# fullCURRENT_power_motor_drive.net
KiCad netlist of a schematic drawn in Altium Designer
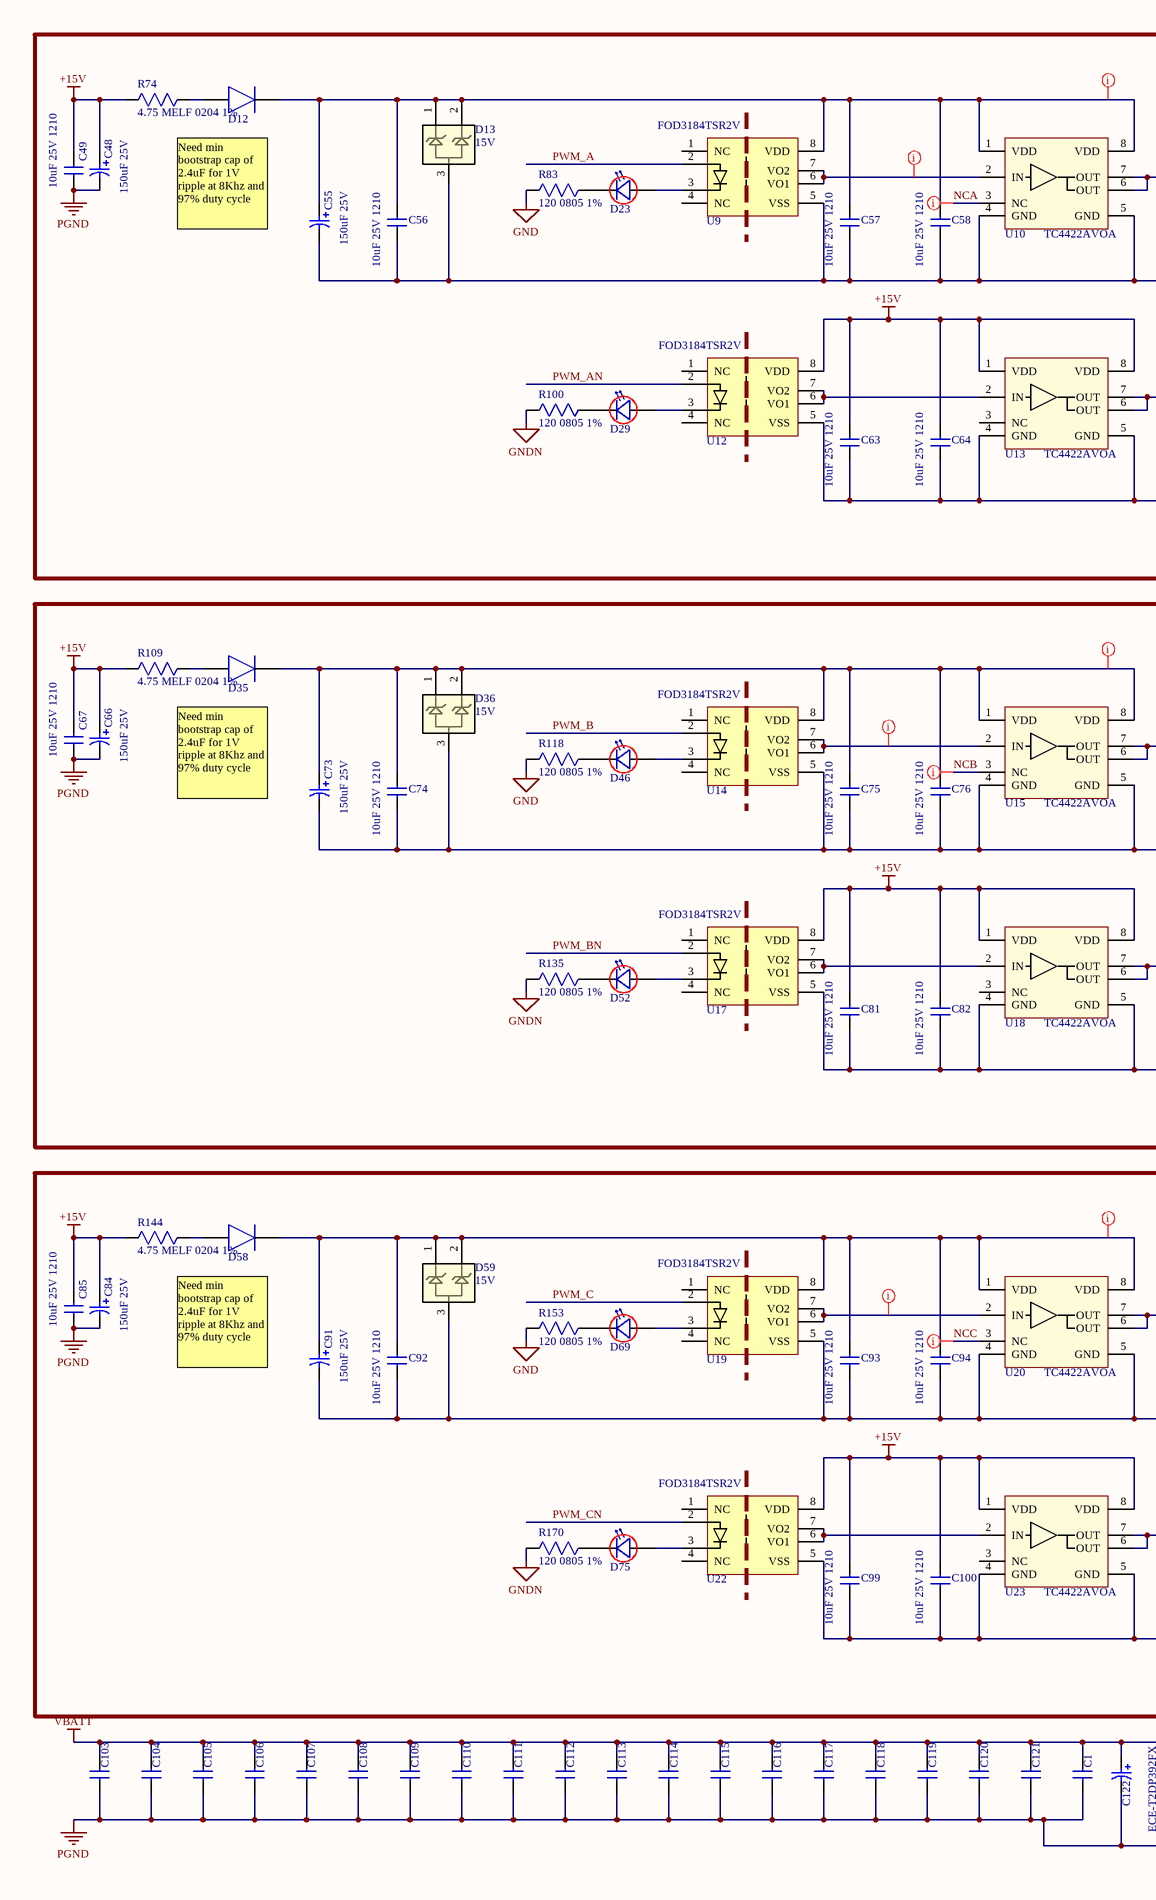
[diagram p0: fullCURRENT power motor drive.SchDoc, left]
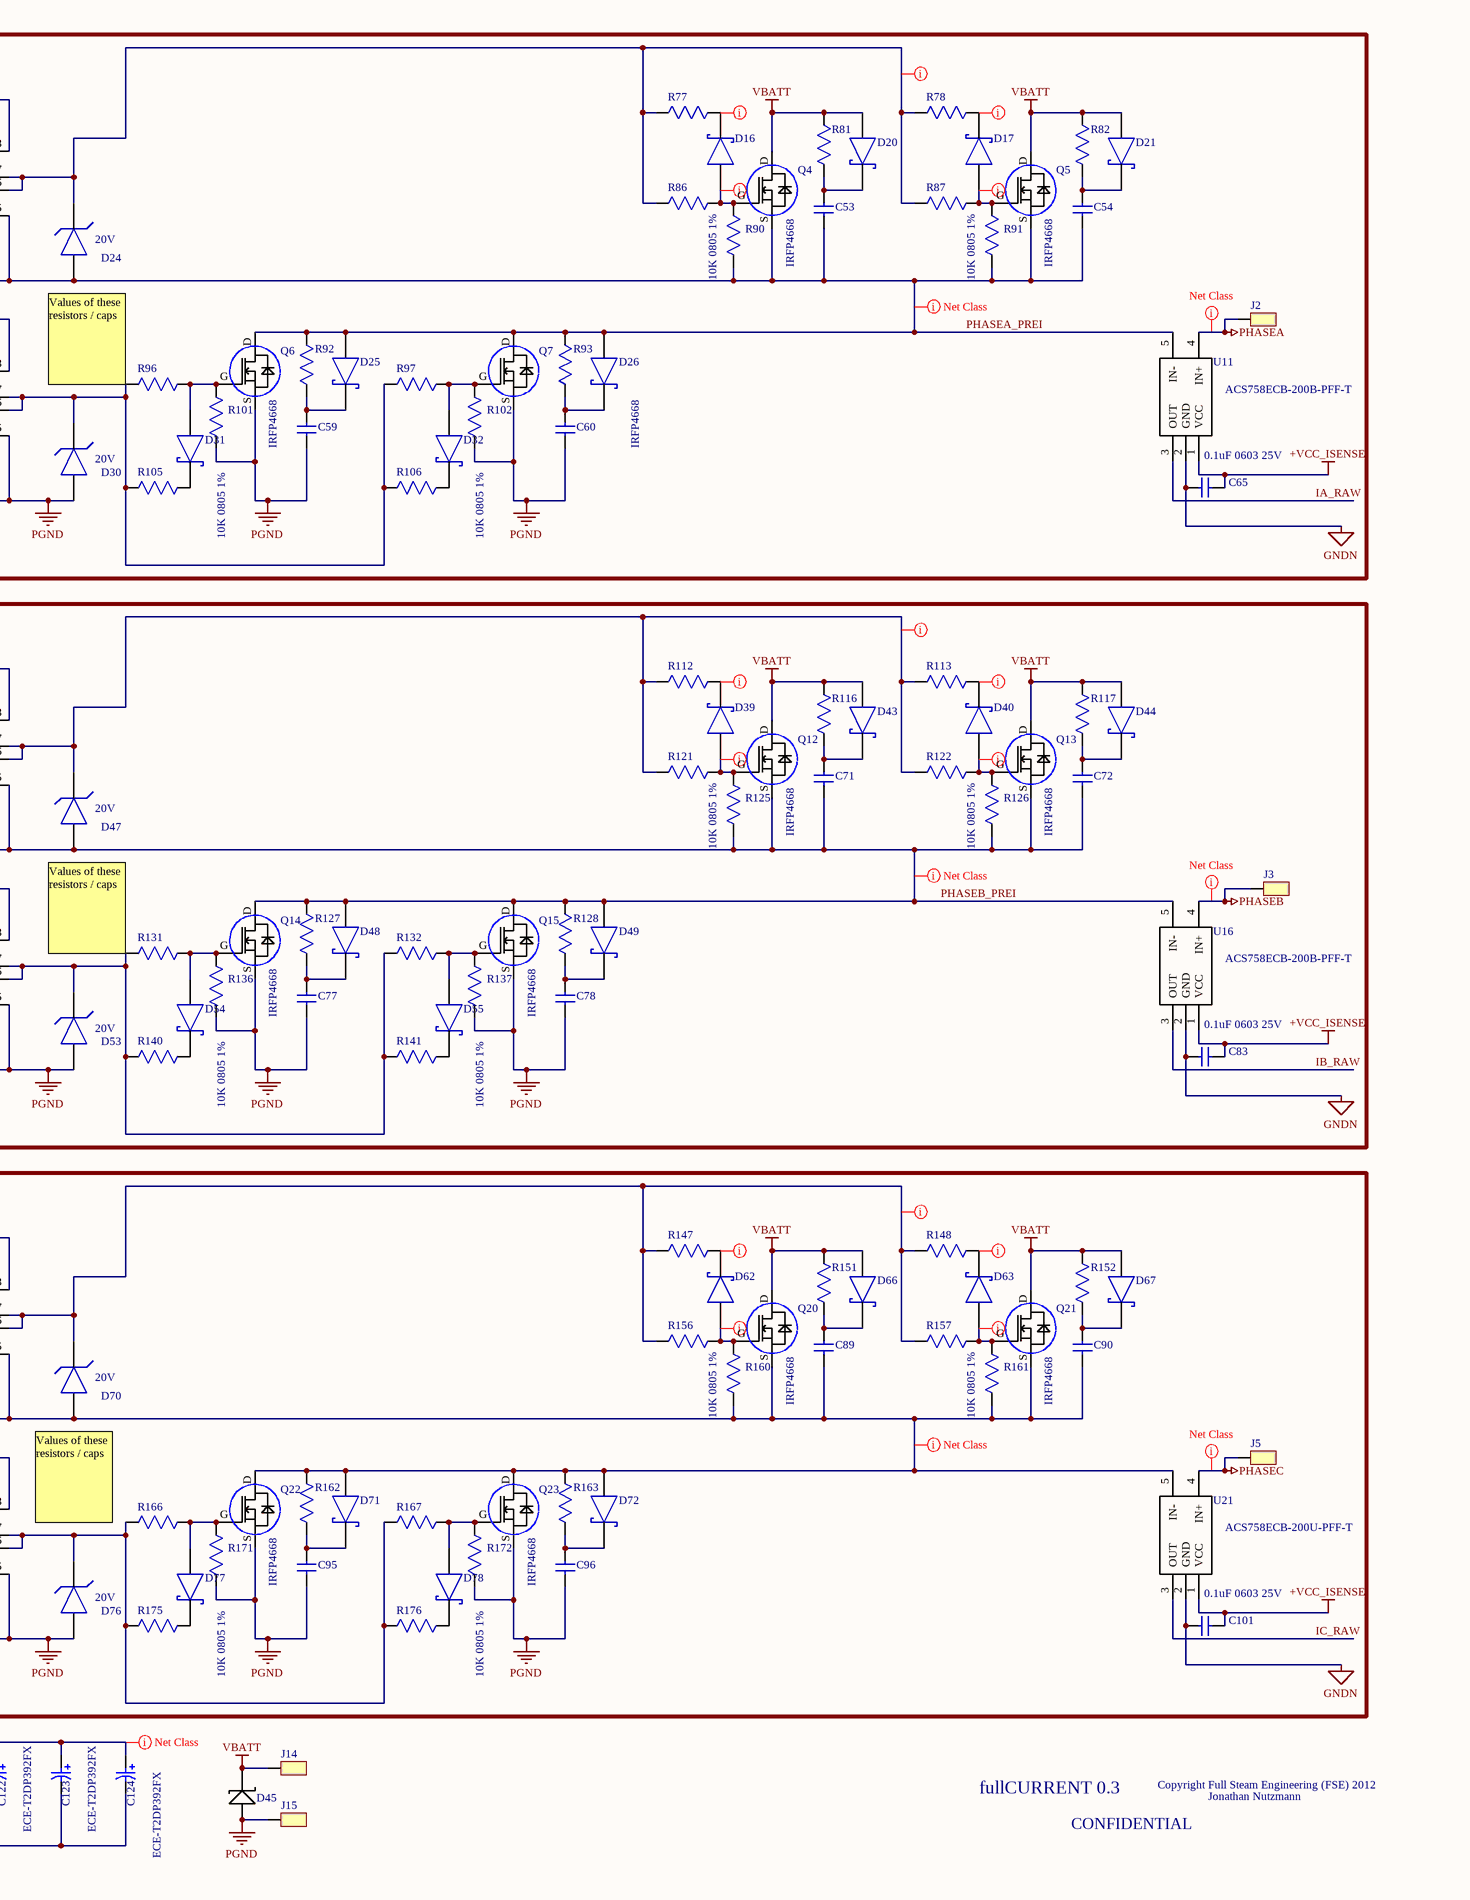
[diagram p1: fullCURRENT power motor drive.SchDoc, right]

(export (version "E")
  (design (tool "Eeschema 10.0.6"))
  (components
    (comp (ref "C1")
      (value "CAP 1210")
      (footprint "1825_CAPACITOR")
      (description "CAP CER 1UF 250V 10% X7R 1825")
      (libsource (lib "altium-import") (part "root_1_C_1210_"))
    )
    (comp (ref "C48")
      (value "150uF 25V")
      (footprint "CAPPR2.5-6.3x11")
      (description "CAP ALUM 150UF 25V 20% RADIAL")
      (fields (field (name "Comment") "C_UMA1E330MDD"))
      (libsource (lib "Nutz") (part "C_UMA1E330MDD"))
    )
    (comp (ref "C49")
      (value "10uF 25V 1210")
      (footprint "1210_Capacitor")
      (description "CAP CER 10UF 25V 10% X7R 1210")
      (fields (field (name "Comment") "CAP 1210"))
      (libsource (lib "c3_SchLib") (part "C_1210"))
    )
    (comp (ref "C53")
      (value "CAP 1210")
      (footprint "1210_Capacitor")
      (description "CAP CERM 1210")
      (libsource (lib "Nutz") (part "C_1210"))
    )
    (comp (ref "C54")
      (value "CAP 1210")
      (footprint "1210_Capacitor")
      (description "CAP CERM 1210")
      (libsource (lib "Nutz") (part "C_1210"))
    )
    (comp (ref "C55")
      (value "150uF 25V")
      (footprint "CAPPR2.5-6.3x11")
      (description "CAP ALUM 150UF 25V 20% RADIAL")
      (fields (field (name "Comment") "C_UMA1E330MDD"))
      (libsource (lib "Nutz") (part "C_UMA1E330MDD"))
    )
    (comp (ref "C56")
      (value "10uF 25V 1210")
      (footprint "1210_Capacitor")
      (description "CAP CER 10UF 25V 10% X7R 1210")
      (fields (field (name "Comment") "CAP 1210"))
      (libsource (lib "c3_SchLib") (part "C_1210"))
    )
    (comp (ref "C57")
      (value "10uF 25V 1210")
      (footprint "1210_Capacitor")
      (description "CAP CER 10UF 25V 10% X7R 1210")
      (fields (field (name "Comment") "CAP 1210"))
      (libsource (lib "c3_SchLib") (part "C_1210"))
    )
    (comp (ref "C58")
      (value "10uF 25V 1210")
      (footprint "1210_Capacitor")
      (description "CAP CER 10UF 25V 10% X7R 1210")
      (fields (field (name "Comment") "CAP 1210"))
      (libsource (lib "c3_SchLib") (part "C_1210"))
    )
    (comp (ref "C59")
      (value "CAP 1210")
      (footprint "1210_Capacitor")
      (description "CAP CERM 1210")
      (libsource (lib "Nutz") (part "C_1210"))
    )
    (comp (ref "C60")
      (value "CAP 1210")
      (footprint "1210_Capacitor")
      (description "CAP CERM 1210")
      (libsource (lib "Nutz") (part "C_1210"))
    )
    (comp (ref "C63")
      (value "10uF 25V 1210")
      (footprint "1210_Capacitor")
      (description "CAP CER 10UF 25V 10% X7R 1210")
      (fields (field (name "Comment") "CAP 1210"))
      (libsource (lib "c3_SchLib") (part "C_1210"))
    )
    (comp (ref "C64")
      (value "10uF 25V 1210")
      (footprint "1210_Capacitor")
      (description "CAP CER 10UF 25V 10% X7R 1210")
      (fields (field (name "Comment") "CAP 1210"))
      (libsource (lib "c3_SchLib") (part "C_1210"))
    )
    (comp (ref "C65")
      (value "0.1uF 0603 25V")
      (footprint "0805_CAPACITOR")
      (description "CAP CERM 0.1uF 0603 X7R")
      (fields (field (name "Comment") "CAP 0603"))
      (libsource (lib "Nutz") (part "C_0603"))
    )
    (comp (ref "C66")
      (value "150uF 25V")
      (footprint "CAPPR2.5-6.3x11")
      (description "CAP ALUM 150UF 25V 20% RADIAL")
      (fields (field (name "Comment") "C_UMA1E330MDD"))
      (libsource (lib "Nutz") (part "C_UMA1E330MDD"))
    )
    (comp (ref "C67")
      (value "10uF 25V 1210")
      (footprint "1210_Capacitor")
      (description "CAP CER 10UF 25V 10% X7R 1210")
      (fields (field (name "Comment") "CAP 1210"))
      (libsource (lib "c3_SchLib") (part "C_1210"))
    )
    (comp (ref "C71")
      (value "CAP 1210")
      (footprint "1210_Capacitor")
      (description "CAP CERM 1210")
      (libsource (lib "Nutz") (part "C_1210"))
    )
    (comp (ref "C72")
      (value "CAP 1210")
      (footprint "1210_Capacitor")
      (description "CAP CERM 1210")
      (libsource (lib "Nutz") (part "C_1210"))
    )
    (comp (ref "C73")
      (value "150uF 25V")
      (footprint "CAPPR2.5-6.3x11")
      (description "CAP ALUM 150UF 25V 20% RADIAL")
      (fields (field (name "Comment") "C_UMA1E330MDD"))
      (libsource (lib "Nutz") (part "C_UMA1E330MDD"))
    )
    (comp (ref "C74")
      (value "10uF 25V 1210")
      (footprint "1210_Capacitor")
      (description "CAP CER 10UF 25V 10% X7R 1210")
      (fields (field (name "Comment") "CAP 1210"))
      (libsource (lib "c3_SchLib") (part "C_1210"))
    )
    (comp (ref "C75")
      (value "10uF 25V 1210")
      (footprint "1210_Capacitor")
      (description "CAP CER 10UF 25V 10% X7R 1210")
      (fields (field (name "Comment") "CAP 1210"))
      (libsource (lib "c3_SchLib") (part "C_1210"))
    )
    (comp (ref "C76")
      (value "10uF 25V 1210")
      (footprint "1210_Capacitor")
      (description "CAP CER 10UF 25V 10% X7R 1210")
      (fields (field (name "Comment") "CAP 1210"))
      (libsource (lib "c3_SchLib") (part "C_1210"))
    )
    (comp (ref "C77")
      (value "CAP 1210")
      (footprint "1210_Capacitor")
      (description "CAP CERM 1210")
      (libsource (lib "Nutz") (part "C_1210"))
    )
    (comp (ref "C78")
      (value "CAP 1210")
      (footprint "1210_Capacitor")
      (description "CAP CERM 1210")
      (libsource (lib "Nutz") (part "C_1210"))
    )
    (comp (ref "C81")
      (value "10uF 25V 1210")
      (footprint "1210_Capacitor")
      (description "CAP CER 10UF 25V 10% X7R 1210")
      (fields (field (name "Comment") "CAP 1210"))
      (libsource (lib "c3_SchLib") (part "C_1210"))
    )
    (comp (ref "C82")
      (value "10uF 25V 1210")
      (footprint "1210_Capacitor")
      (description "CAP CER 10UF 25V 10% X7R 1210")
      (fields (field (name "Comment") "CAP 1210"))
      (libsource (lib "c3_SchLib") (part "C_1210"))
    )
    (comp (ref "C83")
      (value "0.1uF 0603 25V")
      (footprint "0805_CAPACITOR")
      (description "CAP CERM 0.1uF 0603 X7R")
      (fields (field (name "Comment") "CAP 0603"))
      (libsource (lib "Nutz") (part "C_0603"))
    )
    (comp (ref "C84")
      (value "150uF 25V")
      (footprint "CAPPR2.5-6.3x11")
      (description "CAP ALUM 150UF 25V 20% RADIAL")
      (fields (field (name "Comment") "C_UMA1E330MDD"))
      (libsource (lib "Nutz") (part "C_UMA1E330MDD"))
    )
    (comp (ref "C85")
      (value "10uF 25V 1210")
      (footprint "1210_Capacitor")
      (description "CAP CER 10UF 25V 10% X7R 1210")
      (fields (field (name "Comment") "CAP 1210"))
      (libsource (lib "c3_SchLib") (part "C_1210"))
    )
    (comp (ref "C89")
      (value "CAP 1210")
      (footprint "1210_Capacitor")
      (description "CAP CERM 1210")
      (libsource (lib "Nutz") (part "C_1210"))
    )
    (comp (ref "C90")
      (value "CAP 1210")
      (footprint "1210_Capacitor")
      (description "CAP CERM 1210")
      (libsource (lib "Nutz") (part "C_1210"))
    )
    (comp (ref "C91")
      (value "150uF 25V")
      (footprint "CAPPR2.5-6.3x11")
      (description "CAP ALUM 150UF 25V 20% RADIAL")
      (fields (field (name "Comment") "C_UMA1E330MDD"))
      (libsource (lib "Nutz") (part "C_UMA1E330MDD"))
    )
    (comp (ref "C92")
      (value "10uF 25V 1210")
      (footprint "1210_Capacitor")
      (description "CAP CER 10UF 25V 10% X7R 1210")
      (fields (field (name "Comment") "CAP 1210"))
      (libsource (lib "c3_SchLib") (part "C_1210"))
    )
    (comp (ref "C93")
      (value "10uF 25V 1210")
      (footprint "1210_Capacitor")
      (description "CAP CER 10UF 25V 10% X7R 1210")
      (fields (field (name "Comment") "CAP 1210"))
      (libsource (lib "c3_SchLib") (part "C_1210"))
    )
    (comp (ref "C94")
      (value "10uF 25V 1210")
      (footprint "1210_Capacitor")
      (description "CAP CER 10UF 25V 10% X7R 1210")
      (fields (field (name "Comment") "CAP 1210"))
      (libsource (lib "c3_SchLib") (part "C_1210"))
    )
    (comp (ref "C95")
      (value "CAP 1210")
      (footprint "1210_Capacitor")
      (description "CAP CERM 1210")
      (libsource (lib "Nutz") (part "C_1210"))
    )
    (comp (ref "C96")
      (value "CAP 1210")
      (footprint "1210_Capacitor")
      (description "CAP CERM 1210")
      (libsource (lib "Nutz") (part "C_1210"))
    )
    (comp (ref "C99")
      (value "10uF 25V 1210")
      (footprint "1210_Capacitor")
      (description "CAP CER 10UF 25V 10% X7R 1210")
      (fields (field (name "Comment") "CAP 1210"))
      (libsource (lib "c3_SchLib") (part "C_1210"))
    )
    (comp (ref "C100")
      (value "10uF 25V 1210")
      (footprint "1210_Capacitor")
      (description "CAP CER 10UF 25V 10% X7R 1210")
      (fields (field (name "Comment") "CAP 1210"))
      (libsource (lib "c3_SchLib") (part "C_1210"))
    )
    (comp (ref "C101")
      (value "0.1uF 0603 25V")
      (footprint "0805_CAPACITOR")
      (description "CAP CERM 0.1uF 0603 X7R")
      (fields (field (name "Comment") "CAP 0603"))
      (libsource (lib "Nutz") (part "C_0603"))
    )
    (comp (ref "C103")
      (value "CAP 1210")
      (footprint "1825_CAPACITOR")
      (description "CAP CER 1UF 250V 10% X7R 1825")
      (libsource (lib "altium-import") (part "root_1_C_1210_"))
    )
    (comp (ref "C104")
      (value "CAP 1210")
      (footprint "1825_CAPACITOR")
      (description "CAP CER 1UF 250V 10% X7R 1825")
      (libsource (lib "altium-import") (part "root_1_C_1210_"))
    )
    (comp (ref "C105")
      (value "CAP 1210")
      (footprint "1825_CAPACITOR")
      (description "CAP CER 1UF 250V 10% X7R 1825")
      (libsource (lib "altium-import") (part "root_1_C_1210_"))
    )
    (comp (ref "C106")
      (value "CAP 1210")
      (footprint "1825_CAPACITOR")
      (description "CAP CER 1UF 250V 10% X7R 1825")
      (libsource (lib "altium-import") (part "root_1_C_1210_"))
    )
    (comp (ref "C107")
      (value "CAP 1210")
      (footprint "1825_CAPACITOR")
      (description "CAP CER 1UF 250V 10% X7R 1825")
      (libsource (lib "altium-import") (part "root_1_C_1210_"))
    )
    (comp (ref "C108")
      (value "CAP 1210")
      (footprint "1825_CAPACITOR")
      (description "CAP CER 1UF 250V 10% X7R 1825")
      (libsource (lib "altium-import") (part "root_1_C_1210_"))
    )
    (comp (ref "C109")
      (value "CAP 1210")
      (footprint "1825_CAPACITOR")
      (description "CAP CER 1UF 250V 10% X7R 1825")
      (libsource (lib "altium-import") (part "root_1_C_1210_"))
    )
    (comp (ref "C110")
      (value "CAP 1210")
      (footprint "1825_CAPACITOR")
      (description "CAP CER 1UF 250V 10% X7R 1825")
      (libsource (lib "altium-import") (part "root_1_C_1210_"))
    )
    (comp (ref "C111")
      (value "CAP 1210")
      (footprint "1825_CAPACITOR")
      (description "CAP CER 1UF 250V 10% X7R 1825")
      (libsource (lib "altium-import") (part "root_1_C_1210_"))
    )
    (comp (ref "C112")
      (value "CAP 1210")
      (footprint "1825_CAPACITOR")
      (description "CAP CER 1UF 250V 10% X7R 1825")
      (libsource (lib "altium-import") (part "root_1_C_1210_"))
    )
    (comp (ref "C113")
      (value "CAP 1210")
      (footprint "1825_CAPACITOR")
      (description "CAP CER 1UF 250V 10% X7R 1825")
      (libsource (lib "altium-import") (part "root_1_C_1210_"))
    )
    (comp (ref "C114")
      (value "CAP 1210")
      (footprint "1825_CAPACITOR")
      (description "CAP CER 1UF 250V 10% X7R 1825")
      (libsource (lib "altium-import") (part "root_1_C_1210_"))
    )
    (comp (ref "C115")
      (value "CAP 1210")
      (footprint "1825_CAPACITOR")
      (description "CAP CER 1UF 250V 10% X7R 1825")
      (libsource (lib "altium-import") (part "root_1_C_1210_"))
    )
    (comp (ref "C116")
      (value "CAP 1210")
      (footprint "1825_CAPACITOR")
      (description "CAP CER 1UF 250V 10% X7R 1825")
      (libsource (lib "altium-import") (part "root_1_C_1210_"))
    )
    (comp (ref "C117")
      (value "CAP 1210")
      (footprint "1825_CAPACITOR")
      (description "CAP CER 1UF 250V 10% X7R 1825")
      (libsource (lib "altium-import") (part "root_1_C_1210_"))
    )
    (comp (ref "C118")
      (value "CAP 1210")
      (footprint "1825_CAPACITOR")
      (description "CAP CER 1UF 250V 10% X7R 1825")
      (libsource (lib "altium-import") (part "root_1_C_1210_"))
    )
    (comp (ref "C119")
      (value "CAP 1210")
      (footprint "1825_CAPACITOR")
      (description "CAP CER 1UF 250V 10% X7R 1825")
      (libsource (lib "altium-import") (part "root_1_C_1210_"))
    )
    (comp (ref "C120")
      (value "CAP 1210")
      (footprint "1825_CAPACITOR")
      (description "CAP CER 1UF 250V 10% X7R 1825")
      (libsource (lib "altium-import") (part "root_1_C_1210_"))
    )
    (comp (ref "C121")
      (value "CAP 1210")
      (footprint "1825_CAPACITOR")
      (description "CAP CER 1UF 250V 10% X7R 1825")
      (libsource (lib "altium-import") (part "root_1_C_1210_"))
    )
    (comp (ref "C122")
      (value "C_ECE-T2DP392FX")
      (footprint "T-UP Series 4 Pin")
      (description "CAP ALUM 3900UF 200V 20% SNAP")
      (fields (field (name "MANUFACTURER") "Panasonic") (field (name "PART NUMBER") "ECE-T2DP392FX"))
      (libsource (lib "Nutz") (part "C_ECE-T2DP392FX"))
    )
    (comp (ref "C123")
      (value "C_ECE-T2DP392FX")
      (footprint "T-UP Series 4 Pin")
      (description "CAP ALUM 3900UF 200V 20% SNAP")
      (fields (field (name "MANUFACTURER") "Panasonic") (field (name "PART NUMBER") "ECE-T2DP392FX"))
      (libsource (lib "Nutz") (part "C_ECE-T2DP392FX"))
    )
    (comp (ref "C124")
      (value "C_ECE-T2DP392FX")
      (footprint "T-UP Series 4 Pin")
      (description "CAP ALUM 3900UF 200V 20% SNAP")
      (fields (field (name "MANUFACTURER") "Panasonic") (field (name "PART NUMBER") "ECE-T2DP392FX"))
      (libsource (lib "Nutz") (part "C_ECE-T2DP392FX"))
    )
    (comp (ref "D12")
      (value "D_ES1D")
      (footprint "nutz:SMA")
      (description "DIODE ULTRAFAST 200V 1A DO-214AC")
      (libsource (lib "Nutz") (part "D_ES1D"))
    )
    (comp (ref "D13")
      (value "15V")
      (footprint "SOT-23")
      (description "15V TVS SOT23")
      (libsource (lib "altium-import") (part "root_0_SM15_"))
    )
    (comp (ref "D16")
      (value "D_PMEG4050EP,115")
      (footprint "SOD128")
      (description "SCHOTTKY RECT 40V 5A SOD128")
      (fields (field (name "MANUFACTURER") "NXP") (field (name "PART NUMBER") "PMEG4050EP,115"))
      (libsource (lib "Nutz") (part "D_PMEG4050EP,115"))
    )
    (comp (ref "D17")
      (value "D_PMEG4050EP,115")
      (footprint "SOD128")
      (description "SCHOTTKY RECT 40V 5A SOD128")
      (fields (field (name "MANUFACTURER") "NXP") (field (name "PART NUMBER") "PMEG4050EP,115"))
      (libsource (lib "Nutz") (part "D_PMEG4050EP,115"))
    )
    (comp (ref "D20")
      (value "D_MBRS3200T3G")
      (footprint "nutz:SMB")
      (description "DIODE SCHOTTKY 3A 200V SMB")
      (fields (field (name "MANUFACTURER") "ON Semiconductor"))
      (libsource (lib "Nutz") (part "D_MBRS3200T3G"))
    )
    (comp (ref "D21")
      (value "D_MBRS3200T3G")
      (footprint "nutz:SMB")
      (description "DIODE SCHOTTKY 3A 200V SMB")
      (fields (field (name "MANUFACTURER") "ON Semiconductor"))
      (libsource (lib "Nutz") (part "D_MBRS3200T3G"))
    )
    (comp (ref "D23")
      (value "D_LED_0805_RED")
      (footprint "0805P_RED")
      (description "LED RED 0805")
      (libsource (lib "Nutz") (part "D_LED_0805_RED"))
    )
    (comp (ref "D24")
      (value "DIODE TVS 20V 400W UNI 5% SMD")
      (footprint "nutz:SMA")
      (fields (field (name "PART NUMBER") "SMAJ20A") (field (name "STANDOFF VOLTAGE") "20V"))
      (libsource (lib "Nutz") (part "D_SMAJ20A"))
    )
    (comp (ref "D25")
      (value "D_MBRS3200T3G")
      (footprint "nutz:SMB")
      (description "DIODE SCHOTTKY 3A 200V SMB")
      (fields (field (name "MANUFACTURER") "ON Semiconductor"))
      (libsource (lib "Nutz") (part "D_MBRS3200T3G"))
    )
    (comp (ref "D26")
      (value "D_MBRS3200T3G")
      (footprint "nutz:SMB")
      (description "DIODE SCHOTTKY 3A 200V SMB")
      (fields (field (name "MANUFACTURER") "ON Semiconductor"))
      (libsource (lib "Nutz") (part "D_MBRS3200T3G"))
    )
    (comp (ref "D29")
      (value "D_LED_0805_RED")
      (footprint "0805P_RED")
      (description "LED RED 0805")
      (libsource (lib "Nutz") (part "D_LED_0805_RED"))
    )
    (comp (ref "D30")
      (value "DIODE TVS 20V 400W UNI 5% SMD")
      (footprint "nutz:SMA")
      (fields (field (name "PART NUMBER") "SMAJ20A") (field (name "STANDOFF VOLTAGE") "20V"))
      (libsource (lib "Nutz") (part "D_SMAJ20A"))
    )
    (comp (ref "D31")
      (value "D_PMEG4050EP,115")
      (footprint "SOD128")
      (description "SCHOTTKY RECT 40V 5A SOD128")
      (fields (field (name "MANUFACTURER") "NXP") (field (name "PART NUMBER") "PMEG4050EP,115"))
      (libsource (lib "Nutz") (part "D_PMEG4050EP,115"))
    )
    (comp (ref "D32")
      (value "D_PMEG4050EP,115")
      (footprint "SOD128")
      (description "SCHOTTKY RECT 40V 5A SOD128")
      (fields (field (name "MANUFACTURER") "NXP") (field (name "PART NUMBER") "PMEG4050EP,115"))
      (libsource (lib "Nutz") (part "D_PMEG4050EP,115"))
    )
    (comp (ref "D35")
      (value "D_ES1D")
      (footprint "nutz:SMA")
      (description "DIODE ULTRAFAST 200V 1A DO-214AC")
      (libsource (lib "Nutz") (part "D_ES1D"))
    )
    (comp (ref "D36")
      (value "15V")
      (footprint "SOT-23")
      (description "15V TVS SOT23")
      (libsource (lib "altium-import") (part "root_0_SM15_"))
    )
    (comp (ref "D39")
      (value "D_PMEG4050EP,115")
      (footprint "SOD128")
      (description "SCHOTTKY RECT 40V 5A SOD128")
      (fields (field (name "MANUFACTURER") "NXP") (field (name "PART NUMBER") "PMEG4050EP,115"))
      (libsource (lib "Nutz") (part "D_PMEG4050EP,115"))
    )
    (comp (ref "D40")
      (value "D_PMEG4050EP,115")
      (footprint "SOD128")
      (description "SCHOTTKY RECT 40V 5A SOD128")
      (fields (field (name "MANUFACTURER") "NXP") (field (name "PART NUMBER") "PMEG4050EP,115"))
      (libsource (lib "Nutz") (part "D_PMEG4050EP,115"))
    )
    (comp (ref "D43")
      (value "D_MBRS3200T3G")
      (footprint "nutz:SMB")
      (description "DIODE SCHOTTKY 3A 200V SMB")
      (fields (field (name "MANUFACTURER") "ON Semiconductor"))
      (libsource (lib "Nutz") (part "D_MBRS3200T3G"))
    )
    (comp (ref "D44")
      (value "D_MBRS3200T3G")
      (footprint "nutz:SMB")
      (description "DIODE SCHOTTKY 3A 200V SMB")
      (fields (field (name "MANUFACTURER") "ON Semiconductor"))
      (libsource (lib "Nutz") (part "D_MBRS3200T3G"))
    )
    (comp (ref "D45")
      (value "D_5KP180A")
      (footprint "DIODE_TVS_5000W")
      (description "5KP180A")
      (libsource (lib "Nutz") (part "D_5KP180A"))
    )
    (comp (ref "D46")
      (value "D_LED_0805_RED")
      (footprint "0805P_RED")
      (description "LED RED 0805")
      (libsource (lib "Nutz") (part "D_LED_0805_RED"))
    )
    (comp (ref "D47")
      (value "DIODE TVS 20V 400W UNI 5% SMD")
      (footprint "nutz:SMA")
      (fields (field (name "PART NUMBER") "SMAJ20A") (field (name "STANDOFF VOLTAGE") "20V"))
      (libsource (lib "Nutz") (part "D_SMAJ20A"))
    )
    (comp (ref "D48")
      (value "D_MBRS3200T3G")
      (footprint "nutz:SMB")
      (description "DIODE SCHOTTKY 3A 200V SMB")
      (fields (field (name "MANUFACTURER") "ON Semiconductor"))
      (libsource (lib "Nutz") (part "D_MBRS3200T3G"))
    )
    (comp (ref "D49")
      (value "D_MBRS3200T3G")
      (footprint "nutz:SMB")
      (description "DIODE SCHOTTKY 3A 200V SMB")
      (fields (field (name "MANUFACTURER") "ON Semiconductor"))
      (libsource (lib "Nutz") (part "D_MBRS3200T3G"))
    )
    (comp (ref "D52")
      (value "D_LED_0805_RED")
      (footprint "0805P_RED")
      (description "LED RED 0805")
      (libsource (lib "Nutz") (part "D_LED_0805_RED"))
    )
    (comp (ref "D53")
      (value "DIODE TVS 20V 400W UNI 5% SMD")
      (footprint "nutz:SMA")
      (fields (field (name "PART NUMBER") "SMAJ20A") (field (name "STANDOFF VOLTAGE") "20V"))
      (libsource (lib "Nutz") (part "D_SMAJ20A"))
    )
    (comp (ref "D54")
      (value "D_PMEG4050EP,115")
      (footprint "SOD128")
      (description "SCHOTTKY RECT 40V 5A SOD128")
      (fields (field (name "MANUFACTURER") "NXP") (field (name "PART NUMBER") "PMEG4050EP,115"))
      (libsource (lib "Nutz") (part "D_PMEG4050EP,115"))
    )
    (comp (ref "D55")
      (value "D_PMEG4050EP,115")
      (footprint "SOD128")
      (description "SCHOTTKY RECT 40V 5A SOD128")
      (fields (field (name "MANUFACTURER") "NXP") (field (name "PART NUMBER") "PMEG4050EP,115"))
      (libsource (lib "Nutz") (part "D_PMEG4050EP,115"))
    )
    (comp (ref "D58")
      (value "D_ES1D")
      (footprint "nutz:SMA")
      (description "DIODE ULTRAFAST 200V 1A DO-214AC")
      (libsource (lib "Nutz") (part "D_ES1D"))
    )
    (comp (ref "D59")
      (value "15V")
      (footprint "SOT-23")
      (description "15V TVS SOT23")
      (libsource (lib "altium-import") (part "root_0_SM15_"))
    )
    (comp (ref "D62")
      (value "D_PMEG4050EP,115")
      (footprint "SOD128")
      (description "SCHOTTKY RECT 40V 5A SOD128")
      (fields (field (name "MANUFACTURER") "NXP") (field (name "PART NUMBER") "PMEG4050EP,115"))
      (libsource (lib "Nutz") (part "D_PMEG4050EP,115"))
    )
    (comp (ref "D63")
      (value "D_PMEG4050EP,115")
      (footprint "SOD128")
      (description "SCHOTTKY RECT 40V 5A SOD128")
      (fields (field (name "MANUFACTURER") "NXP") (field (name "PART NUMBER") "PMEG4050EP,115"))
      (libsource (lib "Nutz") (part "D_PMEG4050EP,115"))
    )
    (comp (ref "D66")
      (value "D_MBRS3200T3G")
      (footprint "nutz:SMB")
      (description "DIODE SCHOTTKY 3A 200V SMB")
      (fields (field (name "MANUFACTURER") "ON Semiconductor"))
      (libsource (lib "Nutz") (part "D_MBRS3200T3G"))
    )
    (comp (ref "D67")
      (value "D_MBRS3200T3G")
      (footprint "nutz:SMB")
      (description "DIODE SCHOTTKY 3A 200V SMB")
      (fields (field (name "MANUFACTURER") "ON Semiconductor"))
      (libsource (lib "Nutz") (part "D_MBRS3200T3G"))
    )
    (comp (ref "D69")
      (value "D_LED_0805_RED")
      (footprint "0805P_RED")
      (description "LED RED 0805")
      (libsource (lib "Nutz") (part "D_LED_0805_RED"))
    )
    (comp (ref "D70")
      (value "DIODE TVS 20V 400W UNI 5% SMD")
      (footprint "nutz:SMA")
      (fields (field (name "PART NUMBER") "SMAJ20A") (field (name "STANDOFF VOLTAGE") "20V"))
      (libsource (lib "Nutz") (part "D_SMAJ20A"))
    )
    (comp (ref "D71")
      (value "D_MBRS3200T3G")
      (footprint "nutz:SMB")
      (description "DIODE SCHOTTKY 3A 200V SMB")
      (fields (field (name "MANUFACTURER") "ON Semiconductor"))
      (libsource (lib "Nutz") (part "D_MBRS3200T3G"))
    )
    (comp (ref "D72")
      (value "D_MBRS3200T3G")
      (footprint "nutz:SMB")
      (description "DIODE SCHOTTKY 3A 200V SMB")
      (fields (field (name "MANUFACTURER") "ON Semiconductor"))
      (libsource (lib "Nutz") (part "D_MBRS3200T3G"))
    )
    (comp (ref "D75")
      (value "D_LED_0805_RED")
      (footprint "0805P_RED")
      (description "LED RED 0805")
      (libsource (lib "Nutz") (part "D_LED_0805_RED"))
    )
    (comp (ref "D76")
      (value "DIODE TVS 20V 400W UNI 5% SMD")
      (footprint "nutz:SMA")
      (fields (field (name "PART NUMBER") "SMAJ20A") (field (name "STANDOFF VOLTAGE") "20V"))
      (libsource (lib "Nutz") (part "D_SMAJ20A"))
    )
    (comp (ref "D77")
      (value "D_PMEG4050EP,115")
      (footprint "SOD128")
      (description "SCHOTTKY RECT 40V 5A SOD128")
      (fields (field (name "MANUFACTURER") "NXP") (field (name "PART NUMBER") "PMEG4050EP,115"))
      (libsource (lib "Nutz") (part "D_PMEG4050EP,115"))
    )
    (comp (ref "D78")
      (value "D_PMEG4050EP,115")
      (footprint "SOD128")
      (description "SCHOTTKY RECT 40V 5A SOD128")
      (fields (field (name "MANUFACTURER") "NXP") (field (name "PART NUMBER") "PMEG4050EP,115"))
      (libsource (lib "Nutz") (part "D_PMEG4050EP,115"))
    )
    (comp (ref "J2")
      (value "J_POWER ELEMENT 90DEG M8 10PIN")
      (footprint "POWER ELEMENT 90DEG M8 10PIN")
      (fields (field (name "PART NUMBER") "7461108") (field (name "MANUFACTURER") "Wurth"))
      (libsource (lib "Nutz") (part "J_POWER ELEMENT 90DEG M8 10PIN"))
    )
    (comp (ref "J3")
      (value "J_POWER ELEMENT 90DEG M8 10PIN")
      (footprint "POWER ELEMENT 90DEG M8 10PIN")
      (fields (field (name "PART NUMBER") "7461108") (field (name "MANUFACTURER") "Wurth"))
      (libsource (lib "Nutz") (part "J_POWER ELEMENT 90DEG M8 10PIN"))
    )
    (comp (ref "J5")
      (value "J_POWER ELEMENT 90DEG M8 10PIN")
      (footprint "POWER ELEMENT 90DEG M8 10PIN")
      (fields (field (name "PART NUMBER") "7461108") (field (name "MANUFACTURER") "Wurth"))
      (libsource (lib "Nutz") (part "J_POWER ELEMENT 90DEG M8 10PIN"))
    )
    (comp (ref "J14")
      (value "J_POWER ELEMENT 90DEG M8 10PIN")
      (footprint "POWER ELEMENT 90DEG M8 10PIN")
      (fields (field (name "PART NUMBER") "7461108") (field (name "MANUFACTURER") "Wurth"))
      (libsource (lib "Nutz") (part "J_POWER ELEMENT 90DEG M8 10PIN"))
    )
    (comp (ref "J15")
      (value "J_POWER ELEMENT 90DEG M8 10PIN")
      (footprint "POWER ELEMENT 90DEG M8 10PIN")
      (fields (field (name "PART NUMBER") "7461108") (field (name "MANUFACTURER") "Wurth"))
      (libsource (lib "Nutz") (part "J_POWER ELEMENT 90DEG M8 10PIN"))
    )
    (comp (ref "Q4") (value "IRFP4668") (footprint "TO-247-UNDER") (libsource (lib "Nutz") (part "IRFP4668")))
    (comp (ref "Q5") (value "IRFP4668") (footprint "TO-247-UNDER") (libsource (lib "Nutz") (part "IRFP4668")))
    (comp (ref "Q6") (value "IRFP4668") (footprint "TO-247-UNDER") (libsource (lib "Nutz") (part "IRFP4668")))
    (comp (ref "Q7") (value "IRFP4668") (footprint "TO-247-UNDER") (libsource (lib "Nutz") (part "IRFP4668")))
    (comp (ref "Q12")
      (value "IRFP4668")
      (footprint "TO-247-UNDER")
      (libsource (lib "Nutz") (part "IRFP4668"))
    )
    (comp (ref "Q13")
      (value "IRFP4668")
      (footprint "TO-247-UNDER")
      (libsource (lib "Nutz") (part "IRFP4668"))
    )
    (comp (ref "Q14")
      (value "IRFP4668")
      (footprint "TO-247-UNDER")
      (libsource (lib "Nutz") (part "IRFP4668"))
    )
    (comp (ref "Q15")
      (value "IRFP4668")
      (footprint "TO-247-UNDER")
      (libsource (lib "Nutz") (part "IRFP4668"))
    )
    (comp (ref "Q20")
      (value "IRFP4668")
      (footprint "TO-247-UNDER")
      (libsource (lib "Nutz") (part "IRFP4668"))
    )
    (comp (ref "Q21")
      (value "IRFP4668")
      (footprint "TO-247-UNDER")
      (libsource (lib "Nutz") (part "IRFP4668"))
    )
    (comp (ref "Q22")
      (value "IRFP4668")
      (footprint "TO-247-UNDER")
      (libsource (lib "Nutz") (part "IRFP4668"))
    )
    (comp (ref "Q23")
      (value "IRFP4668")
      (footprint "TO-247-UNDER")
      (libsource (lib "Nutz") (part "IRFP4668"))
    )
    (comp (ref "R74")
      (value "4.75 MELF 0204 1%")
      (footprint "MELF 0204")
      (description "RES MELF 0204")
      (libsource (lib "Nutz") (part "R_MELF_0204"))
    )
    (comp (ref "R77")
      (value "RES MELF 0204")
      (footprint "MELF 0204")
      (libsource (lib "Nutz") (part "R_MELF_0204"))
    )
    (comp (ref "R78")
      (value "RES MELF 0204")
      (footprint "MELF 0204")
      (libsource (lib "Nutz") (part "R_MELF_0204"))
    )
    (comp (ref "R81")
      (value "RES MELF 0204")
      (footprint "MELF 0204")
      (libsource (lib "Nutz") (part "R_MELF_0204"))
    )
    (comp (ref "R82")
      (value "RES MELF 0204")
      (footprint "MELF 0204")
      (libsource (lib "Nutz") (part "R_MELF_0204"))
    )
    (comp (ref "R83")
      (value "120 0805 1%")
      (footprint "0603_res")
      (description "RES 0603")
      (libsource (lib "Nutz") (part "R_0603"))
    )
    (comp (ref "R86")
      (value "RES MELF 0204")
      (footprint "MELF 0204")
      (libsource (lib "Nutz") (part "R_MELF_0204"))
    )
    (comp (ref "R87")
      (value "RES MELF 0204")
      (footprint "MELF 0204")
      (libsource (lib "Nutz") (part "R_MELF_0204"))
    )
    (comp (ref "R90")
      (value "10K 0805 1%")
      (footprint "0805_RESISTOR")
      (description "RES 0805")
      (libsource (lib "Nutz") (part "R_0603"))
    )
    (comp (ref "R91")
      (value "10K 0805 1%")
      (footprint "0805_RESISTOR")
      (description "RES 0805")
      (libsource (lib "Nutz") (part "R_0603"))
    )
    (comp (ref "R92")
      (value "RES MELF 0204")
      (footprint "MELF 0204")
      (libsource (lib "Nutz") (part "R_MELF_0204"))
    )
    (comp (ref "R93")
      (value "RES MELF 0204")
      (footprint "MELF 0204")
      (libsource (lib "Nutz") (part "R_MELF_0204"))
    )
    (comp (ref "R96")
      (value "RES MELF 0204")
      (footprint "MELF 0204")
      (libsource (lib "Nutz") (part "R_MELF_0204"))
    )
    (comp (ref "R97")
      (value "RES MELF 0204")
      (footprint "MELF 0204")
      (libsource (lib "Nutz") (part "R_MELF_0204"))
    )
    (comp (ref "R100")
      (value "120 0805 1%")
      (footprint "0603_res")
      (description "RES 0603")
      (libsource (lib "Nutz") (part "R_0603"))
    )
    (comp (ref "R101")
      (value "10K 0805 1%")
      (footprint "0805_RESISTOR")
      (description "RES 0805")
      (libsource (lib "Nutz") (part "R_0603"))
    )
    (comp (ref "R102")
      (value "10K 0805 1%")
      (footprint "0805_RESISTOR")
      (description "RES 0805")
      (libsource (lib "Nutz") (part "R_0603"))
    )
    (comp (ref "R105")
      (value "RES MELF 0204")
      (footprint "MELF 0204")
      (libsource (lib "Nutz") (part "R_MELF_0204"))
    )
    (comp (ref "R106")
      (value "RES MELF 0204")
      (footprint "MELF 0204")
      (libsource (lib "Nutz") (part "R_MELF_0204"))
    )
    (comp (ref "R109")
      (value "4.75 MELF 0204 1%")
      (footprint "MELF 0204")
      (description "RES MELF 0204")
      (libsource (lib "Nutz") (part "R_MELF_0204"))
    )
    (comp (ref "R112")
      (value "RES MELF 0204")
      (footprint "MELF 0204")
      (libsource (lib "Nutz") (part "R_MELF_0204"))
    )
    (comp (ref "R113")
      (value "RES MELF 0204")
      (footprint "MELF 0204")
      (libsource (lib "Nutz") (part "R_MELF_0204"))
    )
    (comp (ref "R116")
      (value "RES MELF 0204")
      (footprint "MELF 0204")
      (libsource (lib "Nutz") (part "R_MELF_0204"))
    )
    (comp (ref "R117")
      (value "RES MELF 0204")
      (footprint "MELF 0204")
      (libsource (lib "Nutz") (part "R_MELF_0204"))
    )
    (comp (ref "R118")
      (value "120 0805 1%")
      (footprint "0603_res")
      (description "RES 0603")
      (libsource (lib "Nutz") (part "R_0603"))
    )
    (comp (ref "R121")
      (value "RES MELF 0204")
      (footprint "MELF 0204")
      (libsource (lib "Nutz") (part "R_MELF_0204"))
    )
    (comp (ref "R122")
      (value "RES MELF 0204")
      (footprint "MELF 0204")
      (libsource (lib "Nutz") (part "R_MELF_0204"))
    )
    (comp (ref "R125")
      (value "10K 0805 1%")
      (footprint "0805_RESISTOR")
      (description "RES 0805")
      (libsource (lib "Nutz") (part "R_0603"))
    )
    (comp (ref "R126")
      (value "10K 0805 1%")
      (footprint "0805_RESISTOR")
      (description "RES 0805")
      (libsource (lib "Nutz") (part "R_0603"))
    )
    (comp (ref "R127")
      (value "RES MELF 0204")
      (footprint "MELF 0204")
      (libsource (lib "Nutz") (part "R_MELF_0204"))
    )
    (comp (ref "R128")
      (value "RES MELF 0204")
      (footprint "MELF 0204")
      (libsource (lib "Nutz") (part "R_MELF_0204"))
    )
    (comp (ref "R131")
      (value "RES MELF 0204")
      (footprint "MELF 0204")
      (libsource (lib "Nutz") (part "R_MELF_0204"))
    )
    (comp (ref "R132")
      (value "RES MELF 0204")
      (footprint "MELF 0204")
      (libsource (lib "Nutz") (part "R_MELF_0204"))
    )
    (comp (ref "R135")
      (value "120 0805 1%")
      (footprint "0603_res")
      (description "RES 0603")
      (libsource (lib "Nutz") (part "R_0603"))
    )
    (comp (ref "R136")
      (value "10K 0805 1%")
      (footprint "0805_RESISTOR")
      (description "RES 0805")
      (libsource (lib "Nutz") (part "R_0603"))
    )
    (comp (ref "R137")
      (value "10K 0805 1%")
      (footprint "0805_RESISTOR")
      (description "RES 0805")
      (libsource (lib "Nutz") (part "R_0603"))
    )
    (comp (ref "R140")
      (value "RES MELF 0204")
      (footprint "MELF 0204")
      (libsource (lib "Nutz") (part "R_MELF_0204"))
    )
    (comp (ref "R141")
      (value "RES MELF 0204")
      (footprint "MELF 0204")
      (libsource (lib "Nutz") (part "R_MELF_0204"))
    )
    (comp (ref "R144")
      (value "4.75 MELF 0204 1%")
      (footprint "MELF 0204")
      (description "RES MELF 0204")
      (libsource (lib "Nutz") (part "R_MELF_0204"))
    )
    (comp (ref "R147")
      (value "RES MELF 0204")
      (footprint "MELF 0204")
      (libsource (lib "Nutz") (part "R_MELF_0204"))
    )
    (comp (ref "R148")
      (value "RES MELF 0204")
      (footprint "MELF 0204")
      (libsource (lib "Nutz") (part "R_MELF_0204"))
    )
    (comp (ref "R151")
      (value "RES MELF 0204")
      (footprint "MELF 0204")
      (libsource (lib "Nutz") (part "R_MELF_0204"))
    )
    (comp (ref "R152")
      (value "RES MELF 0204")
      (footprint "MELF 0204")
      (libsource (lib "Nutz") (part "R_MELF_0204"))
    )
    (comp (ref "R153")
      (value "120 0805 1%")
      (footprint "0603_res")
      (description "RES 0603")
      (libsource (lib "Nutz") (part "R_0603"))
    )
    (comp (ref "R156")
      (value "RES MELF 0204")
      (footprint "MELF 0204")
      (libsource (lib "Nutz") (part "R_MELF_0204"))
    )
    (comp (ref "R157")
      (value "RES MELF 0204")
      (footprint "MELF 0204")
      (libsource (lib "Nutz") (part "R_MELF_0204"))
    )
    (comp (ref "R160")
      (value "10K 0805 1%")
      (footprint "0805_RESISTOR")
      (description "RES 0805")
      (libsource (lib "Nutz") (part "R_0603"))
    )
    (comp (ref "R161")
      (value "10K 0805 1%")
      (footprint "0805_RESISTOR")
      (description "RES 0805")
      (libsource (lib "Nutz") (part "R_0603"))
    )
    (comp (ref "R162")
      (value "RES MELF 0204")
      (footprint "MELF 0204")
      (libsource (lib "Nutz") (part "R_MELF_0204"))
    )
    (comp (ref "R163")
      (value "RES MELF 0204")
      (footprint "MELF 0204")
      (libsource (lib "Nutz") (part "R_MELF_0204"))
    )
    (comp (ref "R166")
      (value "RES MELF 0204")
      (footprint "MELF 0204")
      (libsource (lib "Nutz") (part "R_MELF_0204"))
    )
    (comp (ref "R167")
      (value "RES MELF 0204")
      (footprint "MELF 0204")
      (libsource (lib "Nutz") (part "R_MELF_0204"))
    )
    (comp (ref "R170")
      (value "120 0805 1%")
      (footprint "0603_res")
      (description "RES 0603")
      (libsource (lib "Nutz") (part "R_0603"))
    )
    (comp (ref "R171")
      (value "10K 0805 1%")
      (footprint "0805_RESISTOR")
      (description "RES 0805")
      (libsource (lib "Nutz") (part "R_0603"))
    )
    (comp (ref "R172")
      (value "10K 0805 1%")
      (footprint "0805_RESISTOR")
      (description "RES 0805")
      (libsource (lib "Nutz") (part "R_0603"))
    )
    (comp (ref "R175")
      (value "RES MELF 0204")
      (footprint "MELF 0204")
      (libsource (lib "Nutz") (part "R_MELF_0204"))
    )
    (comp (ref "R176")
      (value "RES MELF 0204")
      (footprint "MELF 0204")
      (libsource (lib "Nutz") (part "R_MELF_0204"))
    )
    (comp (ref "U9")
      (value "U_FOD3184TSR2V")
      (footprint "8-SMD")
      (description "OPTO MOSFET/IGBT GATE DVR 8-SMD")
      (fields (field (name "MANUFACTURER") "Fairchild") (field (name "PART NUMBER") "FOD3184TSR2V"))
      (libsource (lib "Nutz") (part "U_FOD3184TSR2V"))
    )
    (comp (ref "U10")
      (value "TC4422AVOA")
      (footprint "SOIC127P600X175-8N")
      (description "IC MOSFET DVR 9A NON-INV 8SOIC")
      (fields (field (name "MANUFACTURER") "Microchip") (field (name "PART NUMBER") "TC4422AVOA"))
      (libsource (lib "c3_SchLib") (part "U_TC4422AVOA"))
    )
    (comp (ref "U11")
      (value "U_ACS758x-CB-PFF")
      (footprint "ACS758")
      (description "IC SENSOR CURRENT 200A UNI 3-CB")
      (fields (field (name "PART NUMBER") "ACS758ECB-200B-PFF-T") (field (name "MANUFACTURER") "Allegro"))
      (libsource (lib "Nutz") (part "U_ACS758x-CB-PFF"))
    )
    (comp (ref "U12")
      (value "U_FOD3184TSR2V")
      (footprint "8-SMD")
      (description "OPTO MOSFET/IGBT GATE DVR 8-SMD")
      (fields (field (name "MANUFACTURER") "Fairchild") (field (name "PART NUMBER") "FOD3184TSR2V"))
      (libsource (lib "Nutz") (part "U_FOD3184TSR2V"))
    )
    (comp (ref "U13")
      (value "TC4422AVOA")
      (footprint "SOIC127P600X175-8N")
      (description "IC MOSFET DVR 9A NON-INV 8SOIC")
      (fields (field (name "MANUFACTURER") "Microchip") (field (name "PART NUMBER") "TC4422AVOA"))
      (libsource (lib "c3_SchLib") (part "U_TC4422AVOA"))
    )
    (comp (ref "U14")
      (value "U_FOD3184TSR2V")
      (footprint "8-SMD")
      (description "OPTO MOSFET/IGBT GATE DVR 8-SMD")
      (fields (field (name "MANUFACTURER") "Fairchild") (field (name "PART NUMBER") "FOD3184TSR2V"))
      (libsource (lib "Nutz") (part "U_FOD3184TSR2V"))
    )
    (comp (ref "U15")
      (value "TC4422AVOA")
      (footprint "SOIC127P600X175-8N")
      (description "IC MOSFET DVR 9A NON-INV 8SOIC")
      (fields (field (name "MANUFACTURER") "Microchip") (field (name "PART NUMBER") "TC4422AVOA"))
      (libsource (lib "c3_SchLib") (part "U_TC4422AVOA"))
    )
    (comp (ref "U16")
      (value "U_ACS758x-CB-PFF")
      (footprint "ACS758")
      (description "IC SENSOR CURRENT 200A UNI 3-CB")
      (fields (field (name "PART NUMBER") "ACS758ECB-200B-PFF-T") (field (name "MANUFACTURER") "Allegro"))
      (libsource (lib "Nutz") (part "U_ACS758x-CB-PFF"))
    )
    (comp (ref "U17")
      (value "U_FOD3184TSR2V")
      (footprint "8-SMD")
      (description "OPTO MOSFET/IGBT GATE DVR 8-SMD")
      (fields (field (name "MANUFACTURER") "Fairchild") (field (name "PART NUMBER") "FOD3184TSR2V"))
      (libsource (lib "Nutz") (part "U_FOD3184TSR2V"))
    )
    (comp (ref "U18")
      (value "TC4422AVOA")
      (footprint "SOIC127P600X175-8N")
      (description "IC MOSFET DVR 9A NON-INV 8SOIC")
      (fields (field (name "MANUFACTURER") "Microchip") (field (name "PART NUMBER") "TC4422AVOA"))
      (libsource (lib "c3_SchLib") (part "U_TC4422AVOA"))
    )
    (comp (ref "U19")
      (value "U_FOD3184TSR2V")
      (footprint "8-SMD")
      (description "OPTO MOSFET/IGBT GATE DVR 8-SMD")
      (fields (field (name "MANUFACTURER") "Fairchild") (field (name "PART NUMBER") "FOD3184TSR2V"))
      (libsource (lib "Nutz") (part "U_FOD3184TSR2V"))
    )
    (comp (ref "U20")
      (value "TC4422AVOA")
      (footprint "SOIC127P600X175-8N")
      (description "IC MOSFET DVR 9A NON-INV 8SOIC")
      (fields (field (name "MANUFACTURER") "Microchip") (field (name "PART NUMBER") "TC4422AVOA"))
      (libsource (lib "c3_SchLib") (part "U_TC4422AVOA"))
    )
    (comp (ref "U21")
      (value "U_ACS758x-CB-PFF")
      (footprint "ACS758")
      (description "IC SENSOR CURRENT 200A UNI 3-CB")
      (fields (field (name "PART NUMBER") "ACS758ECB-200U-PFF-T") (field (name "MANUFACTURER") "Allegro"))
      (libsource (lib "Nutz") (part "U_ACS758x-CB-PFF"))
    )
    (comp (ref "U22")
      (value "U_FOD3184TSR2V")
      (footprint "8-SMD")
      (description "OPTO MOSFET/IGBT GATE DVR 8-SMD")
      (fields (field (name "MANUFACTURER") "Fairchild") (field (name "PART NUMBER") "FOD3184TSR2V"))
      (libsource (lib "Nutz") (part "U_FOD3184TSR2V"))
    )
    (comp (ref "U23")
      (value "TC4422AVOA")
      (footprint "SOIC127P600X175-8N")
      (description "IC MOSFET DVR 9A NON-INV 8SOIC")
      (fields (field (name "MANUFACTURER") "Microchip") (field (name "PART NUMBER") "TC4422AVOA"))
      (libsource (lib "c3_SchLib") (part "U_TC4422AVOA"))
    )
  )
  (nets
    (net (code "1") (name "+15V") (class "Default")
      (node (ref "C100") (pin "1") (pinfunction "1_1") (pintype "passive"))
      (node (ref "C48") (pin "1") (pinfunction "1_1") (pintype "passive"))
      (node (ref "C49") (pin "1") (pinfunction "1_1") (pintype "passive"))
      (node (ref "C63") (pin "1") (pinfunction "1_1") (pintype "passive"))
      (node (ref "C64") (pin "1") (pinfunction "1_1") (pintype "passive"))
      (node (ref "C66") (pin "1") (pinfunction "1_1") (pintype "passive"))
      (node (ref "C67") (pin "1") (pinfunction "1_1") (pintype "passive"))
      (node (ref "C81") (pin "1") (pinfunction "1_1") (pintype "passive"))
      (node (ref "C82") (pin "1") (pinfunction "1_1") (pintype "passive"))
      (node (ref "C84") (pin "1") (pinfunction "1_1") (pintype "passive"))
      (node (ref "C85") (pin "1") (pinfunction "1_1") (pintype "passive"))
      (node (ref "C99") (pin "1") (pinfunction "1_1") (pintype "passive"))
      (node (ref "R109") (pin "2") (pinfunction "2_2") (pintype "passive"))
      (node (ref "R144") (pin "2") (pinfunction "2_2") (pintype "passive"))
      (node (ref "R74") (pin "2") (pinfunction "2_2") (pintype "passive"))
      (node (ref "U12") (pin "8") (pinfunction "VDD_8") (pintype "passive"))
      (node (ref "U13") (pin "1") (pinfunction "VDD_1") (pintype "passive"))
      (node (ref "U13") (pin "8") (pinfunction "VDD_8") (pintype "passive"))
      (node (ref "U17") (pin "8") (pinfunction "VDD_8") (pintype "passive"))
      (node (ref "U18") (pin "1") (pinfunction "VDD_1") (pintype "passive"))
      (node (ref "U18") (pin "8") (pinfunction "VDD_8") (pintype "passive"))
      (node (ref "U22") (pin "8") (pinfunction "VDD_8") (pintype "passive"))
      (node (ref "U23") (pin "1") (pinfunction "VDD_1") (pintype "passive"))
      (node (ref "U23") (pin "8") (pinfunction "VDD_8") (pintype "passive"))
    )
    (net (code "2") (name "+VCC_ISENSE") (class "Default")
      (node (ref "C101") (pin "1") (pinfunction "1_1") (pintype "passive"))
      (node (ref "C65") (pin "1") (pinfunction "1_1") (pintype "passive"))
      (node (ref "C83") (pin "1") (pinfunction "1_1") (pintype "passive"))
      (node (ref "U11") (pin "1") (pinfunction "VCC_1") (pintype "passive"))
      (node (ref "U16") (pin "1") (pinfunction "VCC_1") (pintype "passive"))
      (node (ref "U21") (pin "1") (pinfunction "VCC_1") (pintype "passive"))
    )
    (net (code "3") (name "/IA_RAW") (class "Default")
      (node (ref "U11") (pin "3") (pinfunction "OUT_3") (pintype "passive"))
    )
    (net (code "4") (name "/IB_RAW") (class "Default")
      (node (ref "U16") (pin "3") (pinfunction "OUT_3") (pintype "passive"))
    )
    (net (code "5") (name "/IC_RAW") (class "Default")
      (node (ref "U21") (pin "3") (pinfunction "OUT_3") (pintype "passive"))
    )
    (net (code "6") (name "/NCA") (class "Default")
      (node (ref "U10") (pin "3") (pinfunction "NC_3") (pintype "passive"))
    )
    (net (code "7") (name "/NCB") (class "Default")
      (node (ref "U15") (pin "3") (pinfunction "NC_3") (pintype "passive"))
    )
    (net (code "8") (name "/NCC") (class "Default")
      (node (ref "U20") (pin "3") (pinfunction "NC_3") (pintype "passive"))
    )
    (net (code "9") (name "/PHASEA_PREI") (class "Default")
      (node (ref "C53") (pin "2") (pinfunction "2_2") (pintype "passive"))
      (node (ref "C54") (pin "2") (pinfunction "2_2") (pintype "passive"))
      (node (ref "C55") (pin "2") (pinfunction "2_2") (pintype "passive"))
      (node (ref "C56") (pin "2") (pinfunction "2_2") (pintype "passive"))
      (node (ref "C57") (pin "2") (pinfunction "2_2") (pintype "passive"))
      (node (ref "C58") (pin "2") (pinfunction "2_2") (pintype "passive"))
      (node (ref "D13") (pin "3") (pinfunction "3_3") (pintype "passive"))
      (node (ref "D24") (pin "A") (pinfunction "A_A") (pintype "passive"))
      (node (ref "D25") (pin "A") (pinfunction "A_A") (pintype "passive"))
      (node (ref "D26") (pin "A") (pinfunction "A_A") (pintype "passive"))
      (node (ref "Q4") (pin "S") (pinfunction "Source_S") (pintype "passive"))
      (node (ref "Q5") (pin "S") (pinfunction "Source_S") (pintype "passive"))
      (node (ref "Q6") (pin "D") (pinfunction "Drain_D") (pintype "passive"))
      (node (ref "Q7") (pin "D") (pinfunction "Drain_D") (pintype "passive"))
      (node (ref "R90") (pin "2") (pinfunction "2_2") (pintype "passive"))
      (node (ref "R91") (pin "2") (pinfunction "2_2") (pintype "passive"))
      (node (ref "R92") (pin "1") (pinfunction "1_1") (pintype "passive"))
      (node (ref "R93") (pin "1") (pinfunction "1_1") (pintype "passive"))
      (node (ref "U10") (pin "4") (pinfunction "GND_4") (pintype "passive"))
      (node (ref "U10") (pin "5") (pinfunction "GND_5") (pintype "passive"))
      (node (ref "U11") (pin "5") (pinfunction "IN-_5") (pintype "passive"))
      (node (ref "U9") (pin "5") (pinfunction "VSS_5") (pintype "passive"))
    )
    (net (code "10") (name "/PHASEB_PREI") (class "Default")
      (node (ref "C71") (pin "2") (pinfunction "2_2") (pintype "passive"))
      (node (ref "C72") (pin "2") (pinfunction "2_2") (pintype "passive"))
      (node (ref "C73") (pin "2") (pinfunction "2_2") (pintype "passive"))
      (node (ref "C74") (pin "2") (pinfunction "2_2") (pintype "passive"))
      (node (ref "C75") (pin "2") (pinfunction "2_2") (pintype "passive"))
      (node (ref "C76") (pin "2") (pinfunction "2_2") (pintype "passive"))
      (node (ref "D36") (pin "3") (pinfunction "3_3") (pintype "passive"))
      (node (ref "D47") (pin "A") (pinfunction "A_A") (pintype "passive"))
      (node (ref "D48") (pin "A") (pinfunction "A_A") (pintype "passive"))
      (node (ref "D49") (pin "A") (pinfunction "A_A") (pintype "passive"))
      (node (ref "Q12") (pin "S") (pinfunction "Source_S") (pintype "passive"))
      (node (ref "Q13") (pin "S") (pinfunction "Source_S") (pintype "passive"))
      (node (ref "Q14") (pin "D") (pinfunction "Drain_D") (pintype "passive"))
      (node (ref "Q15") (pin "D") (pinfunction "Drain_D") (pintype "passive"))
      (node (ref "R125") (pin "2") (pinfunction "2_2") (pintype "passive"))
      (node (ref "R126") (pin "2") (pinfunction "2_2") (pintype "passive"))
      (node (ref "R127") (pin "1") (pinfunction "1_1") (pintype "passive"))
      (node (ref "R128") (pin "1") (pinfunction "1_1") (pintype "passive"))
      (node (ref "U14") (pin "5") (pinfunction "VSS_5") (pintype "passive"))
      (node (ref "U15") (pin "4") (pinfunction "GND_4") (pintype "passive"))
      (node (ref "U15") (pin "5") (pinfunction "GND_5") (pintype "passive"))
      (node (ref "U16") (pin "5") (pinfunction "IN-_5") (pintype "passive"))
    )
    (net (code "11") (name "/PWM_A") (class "Default")
      (node (ref "U9") (pin "2") (pinfunction "2_2") (pintype "passive"))
    )
    (net (code "12") (name "/PWM_AN") (class "Default")
      (node (ref "U12") (pin "2") (pinfunction "2_2") (pintype "passive"))
    )
    (net (code "13") (name "/PWM_B") (class "Default")
      (node (ref "U14") (pin "2") (pinfunction "2_2") (pintype "passive"))
    )
    (net (code "14") (name "/PWM_BN") (class "Default")
      (node (ref "U17") (pin "2") (pinfunction "2_2") (pintype "passive"))
    )
    (net (code "15") (name "/PWM_C") (class "Default")
      (node (ref "U19") (pin "2") (pinfunction "2_2") (pintype "passive"))
    )
    (net (code "16") (name "/PWM_CN") (class "Default")
      (node (ref "U22") (pin "2") (pinfunction "2_2") (pintype "passive"))
    )
    (net (code "17") (name "GND") (class "Default")
      (node (ref "R118") (pin "2") (pinfunction "2_2") (pintype "passive"))
      (node (ref "R153") (pin "2") (pinfunction "2_2") (pintype "passive"))
      (node (ref "R83") (pin "2") (pinfunction "2_2") (pintype "passive"))
    )
    (net (code "18") (name "GNDN") (class "Default")
      (node (ref "C101") (pin "2") (pinfunction "2_2") (pintype "passive"))
      (node (ref "C65") (pin "2") (pinfunction "2_2") (pintype "passive"))
      (node (ref "C83") (pin "2") (pinfunction "2_2") (pintype "passive"))
      (node (ref "R100") (pin "2") (pinfunction "2_2") (pintype "passive"))
      (node (ref "R135") (pin "2") (pinfunction "2_2") (pintype "passive"))
      (node (ref "R170") (pin "2") (pinfunction "2_2") (pintype "passive"))
      (node (ref "U11") (pin "2") (pinfunction "GND_2") (pintype "passive"))
      (node (ref "U16") (pin "2") (pinfunction "GND_2") (pintype "passive"))
      (node (ref "U21") (pin "2") (pinfunction "GND_2") (pintype "passive"))
    )
    (net (code "19") (name "Net-(C53-Pad1)") (class "Default")
      (node (ref "C53") (pin "1") (pinfunction "1_1") (pintype "passive"))
      (node (ref "D20") (pin "K") (pinfunction "K_K") (pintype "passive"))
      (node (ref "R81") (pin "2") (pinfunction "2_2") (pintype "passive"))
    )
    (net (code "20") (name "Net-(C54-Pad1)") (class "Default")
      (node (ref "C54") (pin "1") (pinfunction "1_1") (pintype "passive"))
      (node (ref "D21") (pin "K") (pinfunction "K_K") (pintype "passive"))
      (node (ref "R82") (pin "2") (pinfunction "2_2") (pintype "passive"))
    )
    (net (code "21") (name "Net-(C59-Pad1)") (class "Default")
      (node (ref "C59") (pin "1") (pinfunction "1_1") (pintype "passive"))
      (node (ref "D25") (pin "K") (pinfunction "K_K") (pintype "passive"))
      (node (ref "R92") (pin "2") (pinfunction "2_2") (pintype "passive"))
    )
    (net (code "22") (name "Net-(C60-Pad1)") (class "Default")
      (node (ref "C60") (pin "1") (pinfunction "1_1") (pintype "passive"))
      (node (ref "D26") (pin "K") (pinfunction "K_K") (pintype "passive"))
      (node (ref "R93") (pin "2") (pinfunction "2_2") (pintype "passive"))
    )
    (net (code "23") (name "Net-(C71-Pad1)") (class "Default")
      (node (ref "C71") (pin "1") (pinfunction "1_1") (pintype "passive"))
      (node (ref "D43") (pin "K") (pinfunction "K_K") (pintype "passive"))
      (node (ref "R116") (pin "2") (pinfunction "2_2") (pintype "passive"))
    )
    (net (code "24") (name "Net-(C72-Pad1)") (class "Default")
      (node (ref "C72") (pin "1") (pinfunction "1_1") (pintype "passive"))
      (node (ref "D44") (pin "K") (pinfunction "K_K") (pintype "passive"))
      (node (ref "R117") (pin "2") (pinfunction "2_2") (pintype "passive"))
    )
    (net (code "25") (name "Net-(C77-Pad1)") (class "Default")
      (node (ref "C77") (pin "1") (pinfunction "1_1") (pintype "passive"))
      (node (ref "D48") (pin "K") (pinfunction "K_K") (pintype "passive"))
      (node (ref "R127") (pin "2") (pinfunction "2_2") (pintype "passive"))
    )
    (net (code "26") (name "Net-(C78-Pad1)") (class "Default")
      (node (ref "C78") (pin "1") (pinfunction "1_1") (pintype "passive"))
      (node (ref "D49") (pin "K") (pinfunction "K_K") (pintype "passive"))
      (node (ref "R128") (pin "2") (pinfunction "2_2") (pintype "passive"))
    )
    (net (code "27") (name "Net-(C89-Pad1)") (class "Default")
      (node (ref "C89") (pin "1") (pinfunction "1_1") (pintype "passive"))
      (node (ref "D66") (pin "K") (pinfunction "K_K") (pintype "passive"))
      (node (ref "R151") (pin "2") (pinfunction "2_2") (pintype "passive"))
    )
    (net (code "28") (name "Net-(C90-Pad1)") (class "Default")
      (node (ref "C90") (pin "1") (pinfunction "1_1") (pintype "passive"))
      (node (ref "D67") (pin "K") (pinfunction "K_K") (pintype "passive"))
      (node (ref "R152") (pin "2") (pinfunction "2_2") (pintype "passive"))
    )
    (net (code "29") (name "Net-(C95-Pad1)") (class "Default")
      (node (ref "C95") (pin "1") (pinfunction "1_1") (pintype "passive"))
      (node (ref "D71") (pin "K") (pinfunction "K_K") (pintype "passive"))
      (node (ref "R162") (pin "2") (pinfunction "2_2") (pintype "passive"))
    )
    (net (code "30") (name "Net-(C96-Pad1)") (class "Default")
      (node (ref "C96") (pin "1") (pinfunction "1_1") (pintype "passive"))
      (node (ref "D72") (pin "K") (pinfunction "K_K") (pintype "passive"))
      (node (ref "R163") (pin "2") (pinfunction "2_2") (pintype "passive"))
    )
    (net (code "31") (name "Net-(D12-PadA)") (class "Default")
      (node (ref "D12") (pin "A") (pinfunction "A_A") (pintype "passive"))
      (node (ref "R74") (pin "1") (pinfunction "1_1") (pintype "passive"))
    )
    (net (code "32") (name "Net-(D16-PadK)") (class "Default")
      (node (ref "D16") (pin "K") (pinfunction "K_K") (pintype "passive"))
      (node (ref "R77") (pin "1") (pinfunction "1_1") (pintype "passive"))
    )
    (net (code "33") (name "Net-(D17-PadK)") (class "Default")
      (node (ref "D17") (pin "K") (pinfunction "K_K") (pintype "passive"))
      (node (ref "R78") (pin "1") (pinfunction "1_1") (pintype "passive"))
    )
    (net (code "34") (name "Net-(D23-Anode)") (class "Default")
      (node (ref "D23") (pin "2") (pinfunction "Anode_2") (pintype "passive"))
      (node (ref "U9") (pin "3") (pinfunction "3_3") (pintype "passive"))
    )
    (net (code "35") (name "Net-(D23-Cathode)") (class "Default")
      (node (ref "D23") (pin "1") (pinfunction "Cathode_1") (pintype "passive"))
      (node (ref "R83") (pin "1") (pinfunction "1_1") (pintype "passive"))
    )
    (net (code "36") (name "Net-(D24-PadK)") (class "Default")
      (node (ref "D24") (pin "K") (pinfunction "K_K") (pintype "passive"))
      (node (ref "R77") (pin "2") (pinfunction "2_2") (pintype "passive"))
      (node (ref "R78") (pin "2") (pinfunction "2_2") (pintype "passive"))
      (node (ref "R86") (pin "2") (pinfunction "2_2") (pintype "passive"))
      (node (ref "R87") (pin "2") (pinfunction "2_2") (pintype "passive"))
      (node (ref "U10") (pin "6") (pinfunction "OUT_6") (pintype "passive"))
      (node (ref "U10") (pin "7") (pinfunction "OUT_7") (pintype "passive"))
    )
    (net (code "37") (name "Net-(D29-Anode)") (class "Default")
      (node (ref "D29") (pin "2") (pinfunction "Anode_2") (pintype "passive"))
      (node (ref "U12") (pin "3") (pinfunction "3_3") (pintype "passive"))
    )
    (net (code "38") (name "Net-(D29-Cathode)") (class "Default")
      (node (ref "D29") (pin "1") (pinfunction "Cathode_1") (pintype "passive"))
      (node (ref "R100") (pin "1") (pinfunction "1_1") (pintype "passive"))
    )
    (net (code "39") (name "Net-(D30-PadK)") (class "Default")
      (node (ref "D30") (pin "K") (pinfunction "K_K") (pintype "passive"))
      (node (ref "R105") (pin "2") (pinfunction "2_2") (pintype "passive"))
      (node (ref "R106") (pin "2") (pinfunction "2_2") (pintype "passive"))
      (node (ref "R96") (pin "2") (pinfunction "2_2") (pintype "passive"))
      (node (ref "R97") (pin "2") (pinfunction "2_2") (pintype "passive"))
      (node (ref "U13") (pin "6") (pinfunction "OUT_6") (pintype "passive"))
      (node (ref "U13") (pin "7") (pinfunction "OUT_7") (pintype "passive"))
    )
    (net (code "40") (name "Net-(D31-PadK)") (class "Default")
      (node (ref "D31") (pin "K") (pinfunction "K_K") (pintype "passive"))
      (node (ref "R105") (pin "1") (pinfunction "1_1") (pintype "passive"))
    )
    (net (code "41") (name "Net-(D32-PadK)") (class "Default")
      (node (ref "D32") (pin "K") (pinfunction "K_K") (pintype "passive"))
      (node (ref "R106") (pin "1") (pinfunction "1_1") (pintype "passive"))
    )
    (net (code "42") (name "Net-(D35-PadA)") (class "Default")
      (node (ref "D35") (pin "A") (pinfunction "A_A") (pintype "passive"))
      (node (ref "R109") (pin "1") (pinfunction "1_1") (pintype "passive"))
    )
    (net (code "43") (name "Net-(D39-PadK)") (class "Default")
      (node (ref "D39") (pin "K") (pinfunction "K_K") (pintype "passive"))
      (node (ref "R112") (pin "1") (pinfunction "1_1") (pintype "passive"))
    )
    (net (code "44") (name "Net-(D40-PadK)") (class "Default")
      (node (ref "D40") (pin "K") (pinfunction "K_K") (pintype "passive"))
      (node (ref "R113") (pin "1") (pinfunction "1_1") (pintype "passive"))
    )
    (net (code "45") (name "Net-(D46-Anode)") (class "Default")
      (node (ref "D46") (pin "2") (pinfunction "Anode_2") (pintype "passive"))
      (node (ref "U14") (pin "3") (pinfunction "3_3") (pintype "passive"))
    )
    (net (code "46") (name "Net-(D46-Cathode)") (class "Default")
      (node (ref "D46") (pin "1") (pinfunction "Cathode_1") (pintype "passive"))
      (node (ref "R118") (pin "1") (pinfunction "1_1") (pintype "passive"))
    )
    (net (code "47") (name "Net-(D47-PadK)") (class "Default")
      (node (ref "D47") (pin "K") (pinfunction "K_K") (pintype "passive"))
      (node (ref "R112") (pin "2") (pinfunction "2_2") (pintype "passive"))
      (node (ref "R113") (pin "2") (pinfunction "2_2") (pintype "passive"))
      (node (ref "R121") (pin "2") (pinfunction "2_2") (pintype "passive"))
      (node (ref "R122") (pin "2") (pinfunction "2_2") (pintype "passive"))
      (node (ref "U15") (pin "6") (pinfunction "OUT_6") (pintype "passive"))
      (node (ref "U15") (pin "7") (pinfunction "OUT_7") (pintype "passive"))
    )
    (net (code "48") (name "Net-(D52-Anode)") (class "Default")
      (node (ref "D52") (pin "2") (pinfunction "Anode_2") (pintype "passive"))
      (node (ref "U17") (pin "3") (pinfunction "3_3") (pintype "passive"))
    )
    (net (code "49") (name "Net-(D52-Cathode)") (class "Default")
      (node (ref "D52") (pin "1") (pinfunction "Cathode_1") (pintype "passive"))
      (node (ref "R135") (pin "1") (pinfunction "1_1") (pintype "passive"))
    )
    (net (code "50") (name "Net-(D53-PadK)") (class "Default")
      (node (ref "D53") (pin "K") (pinfunction "K_K") (pintype "passive"))
      (node (ref "R131") (pin "2") (pinfunction "2_2") (pintype "passive"))
      (node (ref "R132") (pin "2") (pinfunction "2_2") (pintype "passive"))
      (node (ref "R140") (pin "2") (pinfunction "2_2") (pintype "passive"))
      (node (ref "R141") (pin "2") (pinfunction "2_2") (pintype "passive"))
      (node (ref "U18") (pin "6") (pinfunction "OUT_6") (pintype "passive"))
      (node (ref "U18") (pin "7") (pinfunction "OUT_7") (pintype "passive"))
    )
    (net (code "51") (name "Net-(D54-PadK)") (class "Default")
      (node (ref "D54") (pin "K") (pinfunction "K_K") (pintype "passive"))
      (node (ref "R140") (pin "1") (pinfunction "1_1") (pintype "passive"))
    )
    (net (code "52") (name "Net-(D55-PadK)") (class "Default")
      (node (ref "D55") (pin "K") (pinfunction "K_K") (pintype "passive"))
      (node (ref "R141") (pin "1") (pinfunction "1_1") (pintype "passive"))
    )
    (net (code "53") (name "Net-(D58-PadA)") (class "Default")
      (node (ref "D58") (pin "A") (pinfunction "A_A") (pintype "passive"))
      (node (ref "R144") (pin "1") (pinfunction "1_1") (pintype "passive"))
    )
    (net (code "54") (name "Net-(D62-PadK)") (class "Default")
      (node (ref "D62") (pin "K") (pinfunction "K_K") (pintype "passive"))
      (node (ref "R147") (pin "1") (pinfunction "1_1") (pintype "passive"))
    )
    (net (code "55") (name "Net-(D63-PadK)") (class "Default")
      (node (ref "D63") (pin "K") (pinfunction "K_K") (pintype "passive"))
      (node (ref "R148") (pin "1") (pinfunction "1_1") (pintype "passive"))
    )
    (net (code "56") (name "Net-(D69-Anode)") (class "Default")
      (node (ref "D69") (pin "2") (pinfunction "Anode_2") (pintype "passive"))
      (node (ref "U19") (pin "3") (pinfunction "3_3") (pintype "passive"))
    )
    (net (code "57") (name "Net-(D69-Cathode)") (class "Default")
      (node (ref "D69") (pin "1") (pinfunction "Cathode_1") (pintype "passive"))
      (node (ref "R153") (pin "1") (pinfunction "1_1") (pintype "passive"))
    )
    (net (code "58") (name "Net-(D70-PadK)") (class "Default")
      (node (ref "D70") (pin "K") (pinfunction "K_K") (pintype "passive"))
      (node (ref "R147") (pin "2") (pinfunction "2_2") (pintype "passive"))
      (node (ref "R148") (pin "2") (pinfunction "2_2") (pintype "passive"))
      (node (ref "R156") (pin "2") (pinfunction "2_2") (pintype "passive"))
      (node (ref "R157") (pin "2") (pinfunction "2_2") (pintype "passive"))
      (node (ref "U20") (pin "6") (pinfunction "OUT_6") (pintype "passive"))
      (node (ref "U20") (pin "7") (pinfunction "OUT_7") (pintype "passive"))
    )
    (net (code "59") (name "Net-(D75-Anode)") (class "Default")
      (node (ref "D75") (pin "2") (pinfunction "Anode_2") (pintype "passive"))
      (node (ref "U22") (pin "3") (pinfunction "3_3") (pintype "passive"))
    )
    (net (code "60") (name "Net-(D75-Cathode)") (class "Default")
      (node (ref "D75") (pin "1") (pinfunction "Cathode_1") (pintype "passive"))
      (node (ref "R170") (pin "1") (pinfunction "1_1") (pintype "passive"))
    )
    (net (code "61") (name "Net-(D76-PadK)") (class "Default")
      (node (ref "D76") (pin "K") (pinfunction "K_K") (pintype "passive"))
      (node (ref "R166") (pin "2") (pinfunction "2_2") (pintype "passive"))
      (node (ref "R167") (pin "2") (pinfunction "2_2") (pintype "passive"))
      (node (ref "R175") (pin "2") (pinfunction "2_2") (pintype "passive"))
      (node (ref "R176") (pin "2") (pinfunction "2_2") (pintype "passive"))
      (node (ref "U23") (pin "6") (pinfunction "OUT_6") (pintype "passive"))
      (node (ref "U23") (pin "7") (pinfunction "OUT_7") (pintype "passive"))
    )
    (net (code "62") (name "Net-(D77-PadK)") (class "Default")
      (node (ref "D77") (pin "K") (pinfunction "K_K") (pintype "passive"))
      (node (ref "R175") (pin "1") (pinfunction "1_1") (pintype "passive"))
    )
    (net (code "63") (name "Net-(D78-PadK)") (class "Default")
      (node (ref "D78") (pin "K") (pinfunction "K_K") (pintype "passive"))
      (node (ref "R176") (pin "1") (pinfunction "1_1") (pintype "passive"))
    )
    (net (code "64") (name "Net-(Q4-Gate)") (class "Default")
      (node (ref "D16") (pin "A") (pinfunction "A_A") (pintype "passive"))
      (node (ref "Q4") (pin "G") (pinfunction "Gate_G") (pintype "passive"))
      (node (ref "R86") (pin "1") (pinfunction "1_1") (pintype "passive"))
      (node (ref "R90") (pin "1") (pinfunction "1_1") (pintype "passive"))
    )
    (net (code "65") (name "Net-(Q5-Gate)") (class "Default")
      (node (ref "D17") (pin "A") (pinfunction "A_A") (pintype "passive"))
      (node (ref "Q5") (pin "G") (pinfunction "Gate_G") (pintype "passive"))
      (node (ref "R87") (pin "1") (pinfunction "1_1") (pintype "passive"))
      (node (ref "R91") (pin "1") (pinfunction "1_1") (pintype "passive"))
    )
    (net (code "66") (name "Net-(Q6-Gate)") (class "Default")
      (node (ref "D31") (pin "A") (pinfunction "A_A") (pintype "passive"))
      (node (ref "Q6") (pin "G") (pinfunction "Gate_G") (pintype "passive"))
      (node (ref "R101") (pin "1") (pinfunction "1_1") (pintype "passive"))
      (node (ref "R96") (pin "1") (pinfunction "1_1") (pintype "passive"))
    )
    (net (code "67") (name "Net-(Q7-Gate)") (class "Default")
      (node (ref "D32") (pin "A") (pinfunction "A_A") (pintype "passive"))
      (node (ref "Q7") (pin "G") (pinfunction "Gate_G") (pintype "passive"))
      (node (ref "R102") (pin "1") (pinfunction "1_1") (pintype "passive"))
      (node (ref "R97") (pin "1") (pinfunction "1_1") (pintype "passive"))
    )
    (net (code "68") (name "Net-(Q12-Gate)") (class "Default")
      (node (ref "D39") (pin "A") (pinfunction "A_A") (pintype "passive"))
      (node (ref "Q12") (pin "G") (pinfunction "Gate_G") (pintype "passive"))
      (node (ref "R121") (pin "1") (pinfunction "1_1") (pintype "passive"))
      (node (ref "R125") (pin "1") (pinfunction "1_1") (pintype "passive"))
    )
    (net (code "69") (name "Net-(Q13-Gate)") (class "Default")
      (node (ref "D40") (pin "A") (pinfunction "A_A") (pintype "passive"))
      (node (ref "Q13") (pin "G") (pinfunction "Gate_G") (pintype "passive"))
      (node (ref "R122") (pin "1") (pinfunction "1_1") (pintype "passive"))
      (node (ref "R126") (pin "1") (pinfunction "1_1") (pintype "passive"))
    )
    (net (code "70") (name "Net-(Q14-Gate)") (class "Default")
      (node (ref "D54") (pin "A") (pinfunction "A_A") (pintype "passive"))
      (node (ref "Q14") (pin "G") (pinfunction "Gate_G") (pintype "passive"))
      (node (ref "R131") (pin "1") (pinfunction "1_1") (pintype "passive"))
      (node (ref "R136") (pin "1") (pinfunction "1_1") (pintype "passive"))
    )
    (net (code "71") (name "Net-(Q15-Gate)") (class "Default")
      (node (ref "D55") (pin "A") (pinfunction "A_A") (pintype "passive"))
      (node (ref "Q15") (pin "G") (pinfunction "Gate_G") (pintype "passive"))
      (node (ref "R132") (pin "1") (pinfunction "1_1") (pintype "passive"))
      (node (ref "R137") (pin "1") (pinfunction "1_1") (pintype "passive"))
    )
    (net (code "72") (name "Net-(Q20-Gate)") (class "Default")
      (node (ref "D62") (pin "A") (pinfunction "A_A") (pintype "passive"))
      (node (ref "Q20") (pin "G") (pinfunction "Gate_G") (pintype "passive"))
      (node (ref "R156") (pin "1") (pinfunction "1_1") (pintype "passive"))
      (node (ref "R160") (pin "1") (pinfunction "1_1") (pintype "passive"))
    )
    (net (code "73") (name "Net-(Q20-Source)") (class "Default")
      (node (ref "C89") (pin "2") (pinfunction "2_2") (pintype "passive"))
      (node (ref "C90") (pin "2") (pinfunction "2_2") (pintype "passive"))
      (node (ref "C91") (pin "2") (pinfunction "2_2") (pintype "passive"))
      (node (ref "C92") (pin "2") (pinfunction "2_2") (pintype "passive"))
      (node (ref "C93") (pin "2") (pinfunction "2_2") (pintype "passive"))
      (node (ref "C94") (pin "2") (pinfunction "2_2") (pintype "passive"))
      (node (ref "D59") (pin "3") (pinfunction "3_3") (pintype "passive"))
      (node (ref "D70") (pin "A") (pinfunction "A_A") (pintype "passive"))
      (node (ref "D71") (pin "A") (pinfunction "A_A") (pintype "passive"))
      (node (ref "D72") (pin "A") (pinfunction "A_A") (pintype "passive"))
      (node (ref "Q20") (pin "S") (pinfunction "Source_S") (pintype "passive"))
      (node (ref "Q21") (pin "S") (pinfunction "Source_S") (pintype "passive"))
      (node (ref "Q22") (pin "D") (pinfunction "Drain_D") (pintype "passive"))
      (node (ref "Q23") (pin "D") (pinfunction "Drain_D") (pintype "passive"))
      (node (ref "R160") (pin "2") (pinfunction "2_2") (pintype "passive"))
      (node (ref "R161") (pin "2") (pinfunction "2_2") (pintype "passive"))
      (node (ref "R162") (pin "1") (pinfunction "1_1") (pintype "passive"))
      (node (ref "R163") (pin "1") (pinfunction "1_1") (pintype "passive"))
      (node (ref "U19") (pin "5") (pinfunction "VSS_5") (pintype "passive"))
      (node (ref "U20") (pin "4") (pinfunction "GND_4") (pintype "passive"))
      (node (ref "U20") (pin "5") (pinfunction "GND_5") (pintype "passive"))
      (node (ref "U21") (pin "5") (pinfunction "IN-_5") (pintype "passive"))
    )
    (net (code "74") (name "Net-(Q21-Gate)") (class "Default")
      (node (ref "D63") (pin "A") (pinfunction "A_A") (pintype "passive"))
      (node (ref "Q21") (pin "G") (pinfunction "Gate_G") (pintype "passive"))
      (node (ref "R157") (pin "1") (pinfunction "1_1") (pintype "passive"))
      (node (ref "R161") (pin "1") (pinfunction "1_1") (pintype "passive"))
    )
    (net (code "75") (name "Net-(Q22-Gate)") (class "Default")
      (node (ref "D77") (pin "A") (pinfunction "A_A") (pintype "passive"))
      (node (ref "Q22") (pin "G") (pinfunction "Gate_G") (pintype "passive"))
      (node (ref "R166") (pin "1") (pinfunction "1_1") (pintype "passive"))
      (node (ref "R171") (pin "1") (pinfunction "1_1") (pintype "passive"))
    )
    (net (code "76") (name "Net-(Q23-Gate)") (class "Default")
      (node (ref "D78") (pin "A") (pinfunction "A_A") (pintype "passive"))
      (node (ref "Q23") (pin "G") (pinfunction "Gate_G") (pintype "passive"))
      (node (ref "R167") (pin "1") (pinfunction "1_1") (pintype "passive"))
      (node (ref "R172") (pin "1") (pinfunction "1_1") (pintype "passive"))
    )
    (net (code "77") (name "Net-(U9-VDD)") (class "Default")
      (node (ref "C55") (pin "1") (pinfunction "1_1") (pintype "passive"))
      (node (ref "C56") (pin "1") (pinfunction "1_1") (pintype "passive"))
      (node (ref "C57") (pin "1") (pinfunction "1_1") (pintype "passive"))
      (node (ref "C58") (pin "1") (pinfunction "1_1") (pintype "passive"))
      (node (ref "D12") (pin "K") (pinfunction "K_K") (pintype "passive"))
      (node (ref "D13") (pin "1") (pinfunction "1_1") (pintype "passive"))
      (node (ref "D13") (pin "2") (pinfunction "2_2") (pintype "passive"))
      (node (ref "U10") (pin "1") (pinfunction "VDD_1") (pintype "passive"))
      (node (ref "U10") (pin "8") (pinfunction "VDD_8") (pintype "passive"))
      (node (ref "U9") (pin "8") (pinfunction "VDD_8") (pintype "passive"))
    )
    (net (code "78") (name "Net-(U10-IN)") (class "Default")
      (node (ref "U10") (pin "2") (pinfunction "IN_2") (pintype "passive"))
      (node (ref "U9") (pin "6") (pinfunction "VO1_6") (pintype "passive"))
      (node (ref "U9") (pin "7") (pinfunction "VO2_7") (pintype "passive"))
    )
    (net (code "79") (name "Net-(U12-VO1)") (class "Default")
      (node (ref "U12") (pin "6") (pinfunction "VO1_6") (pintype "passive"))
      (node (ref "U12") (pin "7") (pinfunction "VO2_7") (pintype "passive"))
      (node (ref "U13") (pin "2") (pinfunction "IN_2") (pintype "passive"))
    )
    (net (code "80") (name "Net-(U14-VDD)") (class "Default")
      (node (ref "C73") (pin "1") (pinfunction "1_1") (pintype "passive"))
      (node (ref "C74") (pin "1") (pinfunction "1_1") (pintype "passive"))
      (node (ref "C75") (pin "1") (pinfunction "1_1") (pintype "passive"))
      (node (ref "C76") (pin "1") (pinfunction "1_1") (pintype "passive"))
      (node (ref "D35") (pin "K") (pinfunction "K_K") (pintype "passive"))
      (node (ref "D36") (pin "1") (pinfunction "1_1") (pintype "passive"))
      (node (ref "D36") (pin "2") (pinfunction "2_2") (pintype "passive"))
      (node (ref "U14") (pin "8") (pinfunction "VDD_8") (pintype "passive"))
      (node (ref "U15") (pin "1") (pinfunction "VDD_1") (pintype "passive"))
      (node (ref "U15") (pin "8") (pinfunction "VDD_8") (pintype "passive"))
    )
    (net (code "81") (name "Net-(U14-VO1)") (class "Default")
      (node (ref "U14") (pin "6") (pinfunction "VO1_6") (pintype "passive"))
      (node (ref "U14") (pin "7") (pinfunction "VO2_7") (pintype "passive"))
      (node (ref "U15") (pin "2") (pinfunction "IN_2") (pintype "passive"))
    )
    (net (code "82") (name "Net-(U17-VO1)") (class "Default")
      (node (ref "U17") (pin "6") (pinfunction "VO1_6") (pintype "passive"))
      (node (ref "U17") (pin "7") (pinfunction "VO2_7") (pintype "passive"))
      (node (ref "U18") (pin "2") (pinfunction "IN_2") (pintype "passive"))
    )
    (net (code "83") (name "Net-(U19-VDD)") (class "Default")
      (node (ref "C91") (pin "1") (pinfunction "1_1") (pintype "passive"))
      (node (ref "C92") (pin "1") (pinfunction "1_1") (pintype "passive"))
      (node (ref "C93") (pin "1") (pinfunction "1_1") (pintype "passive"))
      (node (ref "C94") (pin "1") (pinfunction "1_1") (pintype "passive"))
      (node (ref "D58") (pin "K") (pinfunction "K_K") (pintype "passive"))
      (node (ref "D59") (pin "1") (pinfunction "1_1") (pintype "passive"))
      (node (ref "D59") (pin "2") (pinfunction "2_2") (pintype "passive"))
      (node (ref "U19") (pin "8") (pinfunction "VDD_8") (pintype "passive"))
      (node (ref "U20") (pin "1") (pinfunction "VDD_1") (pintype "passive"))
      (node (ref "U20") (pin "8") (pinfunction "VDD_8") (pintype "passive"))
    )
    (net (code "84") (name "Net-(U19-VO1)") (class "Default")
      (node (ref "U19") (pin "6") (pinfunction "VO1_6") (pintype "passive"))
      (node (ref "U19") (pin "7") (pinfunction "VO2_7") (pintype "passive"))
      (node (ref "U20") (pin "2") (pinfunction "IN_2") (pintype "passive"))
    )
    (net (code "85") (name "Net-(U22-VO1)") (class "Default")
      (node (ref "U22") (pin "6") (pinfunction "VO1_6") (pintype "passive"))
      (node (ref "U22") (pin "7") (pinfunction "VO2_7") (pintype "passive"))
      (node (ref "U23") (pin "2") (pinfunction "IN_2") (pintype "passive"))
    )
    (net (code "86") (name "PGND") (class "Default")
      (node (ref "C1") (pin "2") (pinfunction "2_2") (pintype "passive"))
      (node (ref "C100") (pin "2") (pinfunction "2_2") (pintype "passive"))
      (node (ref "C103") (pin "2") (pinfunction "2_2") (pintype "passive"))
      (node (ref "C104") (pin "2") (pinfunction "2_2") (pintype "passive"))
      (node (ref "C105") (pin "2") (pinfunction "2_2") (pintype "passive"))
      (node (ref "C106") (pin "2") (pinfunction "2_2") (pintype "passive"))
      (node (ref "C107") (pin "2") (pinfunction "2_2") (pintype "passive"))
      (node (ref "C108") (pin "2") (pinfunction "2_2") (pintype "passive"))
      (node (ref "C109") (pin "2") (pinfunction "2_2") (pintype "passive"))
      (node (ref "C110") (pin "2") (pinfunction "2_2") (pintype "passive"))
      (node (ref "C111") (pin "2") (pinfunction "2_2") (pintype "passive"))
      (node (ref "C112") (pin "2") (pinfunction "2_2") (pintype "passive"))
      (node (ref "C113") (pin "2") (pinfunction "2_2") (pintype "passive"))
      (node (ref "C114") (pin "2") (pinfunction "2_2") (pintype "passive"))
      (node (ref "C115") (pin "2") (pinfunction "2_2") (pintype "passive"))
      (node (ref "C116") (pin "2") (pinfunction "2_2") (pintype "passive"))
      (node (ref "C117") (pin "2") (pinfunction "2_2") (pintype "passive"))
      (node (ref "C118") (pin "2") (pinfunction "2_2") (pintype "passive"))
      (node (ref "C119") (pin "2") (pinfunction "2_2") (pintype "passive"))
      (node (ref "C120") (pin "2") (pinfunction "2_2") (pintype "passive"))
      (node (ref "C121") (pin "2") (pinfunction "2_2") (pintype "passive"))
      (node (ref "C122") (pin "2") (pinfunction "2_2") (pintype "passive"))
      (node (ref "C123") (pin "2") (pinfunction "2_2") (pintype "passive"))
      (node (ref "C124") (pin "2") (pinfunction "2_2") (pintype "passive"))
      (node (ref "C48") (pin "2") (pinfunction "2_2") (pintype "passive"))
      (node (ref "C49") (pin "2") (pinfunction "2_2") (pintype "passive"))
      (node (ref "C59") (pin "2") (pinfunction "2_2") (pintype "passive"))
      (node (ref "C60") (pin "2") (pinfunction "2_2") (pintype "passive"))
      (node (ref "C63") (pin "2") (pinfunction "2_2") (pintype "passive"))
      (node (ref "C64") (pin "2") (pinfunction "2_2") (pintype "passive"))
      (node (ref "C66") (pin "2") (pinfunction "2_2") (pintype "passive"))
      (node (ref "C67") (pin "2") (pinfunction "2_2") (pintype "passive"))
      (node (ref "C77") (pin "2") (pinfunction "2_2") (pintype "passive"))
      (node (ref "C78") (pin "2") (pinfunction "2_2") (pintype "passive"))
      (node (ref "C81") (pin "2") (pinfunction "2_2") (pintype "passive"))
      (node (ref "C82") (pin "2") (pinfunction "2_2") (pintype "passive"))
      (node (ref "C84") (pin "2") (pinfunction "2_2") (pintype "passive"))
      (node (ref "C85") (pin "2") (pinfunction "2_2") (pintype "passive"))
      (node (ref "C95") (pin "2") (pinfunction "2_2") (pintype "passive"))
      (node (ref "C96") (pin "2") (pinfunction "2_2") (pintype "passive"))
      (node (ref "C99") (pin "2") (pinfunction "2_2") (pintype "passive"))
      (node (ref "D30") (pin "A") (pinfunction "A_A") (pintype "passive"))
      (node (ref "D45") (pin "A") (pinfunction "Anode_A") (pintype "passive"))
      (node (ref "D53") (pin "A") (pinfunction "A_A") (pintype "passive"))
      (node (ref "D76") (pin "A") (pinfunction "A_A") (pintype "passive"))
      (node (ref "J15") (pin "0") (pinfunction "0_0") (pintype "passive"))
      (node (ref "Q14") (pin "S") (pinfunction "Source_S") (pintype "passive"))
      (node (ref "Q15") (pin "S") (pinfunction "Source_S") (pintype "passive"))
      (node (ref "Q22") (pin "S") (pinfunction "Source_S") (pintype "passive"))
      (node (ref "Q23") (pin "S") (pinfunction "Source_S") (pintype "passive"))
      (node (ref "Q6") (pin "S") (pinfunction "Source_S") (pintype "passive"))
      (node (ref "Q7") (pin "S") (pinfunction "Source_S") (pintype "passive"))
      (node (ref "R101") (pin "2") (pinfunction "2_2") (pintype "passive"))
      (node (ref "R102") (pin "2") (pinfunction "2_2") (pintype "passive"))
      (node (ref "R136") (pin "2") (pinfunction "2_2") (pintype "passive"))
      (node (ref "R137") (pin "2") (pinfunction "2_2") (pintype "passive"))
      (node (ref "R171") (pin "2") (pinfunction "2_2") (pintype "passive"))
      (node (ref "R172") (pin "2") (pinfunction "2_2") (pintype "passive"))
      (node (ref "U12") (pin "5") (pinfunction "VSS_5") (pintype "passive"))
      (node (ref "U13") (pin "4") (pinfunction "GND_4") (pintype "passive"))
      (node (ref "U13") (pin "5") (pinfunction "GND_5") (pintype "passive"))
      (node (ref "U17") (pin "5") (pinfunction "VSS_5") (pintype "passive"))
      (node (ref "U18") (pin "4") (pinfunction "GND_4") (pintype "passive"))
      (node (ref "U18") (pin "5") (pinfunction "GND_5") (pintype "passive"))
      (node (ref "U22") (pin "5") (pinfunction "VSS_5") (pintype "passive"))
      (node (ref "U23") (pin "4") (pinfunction "GND_4") (pintype "passive"))
      (node (ref "U23") (pin "5") (pinfunction "GND_5") (pintype "passive"))
    )
    (net (code "87") (name "PHASEA") (class "Default")
      (node (ref "J2") (pin "0") (pinfunction "0_0") (pintype "passive"))
      (node (ref "U11") (pin "4") (pinfunction "IN+_4") (pintype "passive"))
    )
    (net (code "88") (name "PHASEB") (class "Default")
      (node (ref "J3") (pin "0") (pinfunction "0_0") (pintype "passive"))
      (node (ref "U16") (pin "4") (pinfunction "IN+_4") (pintype "passive"))
    )
    (net (code "89") (name "PHASEC") (class "Default")
      (node (ref "J5") (pin "0") (pinfunction "0_0") (pintype "passive"))
      (node (ref "U21") (pin "4") (pinfunction "IN+_4") (pintype "passive"))
    )
    (net (code "90") (name "VBATT") (class "Default")
      (node (ref "C1") (pin "1") (pinfunction "1_1") (pintype "passive"))
      (node (ref "C103") (pin "1") (pinfunction "1_1") (pintype "passive"))
      (node (ref "C104") (pin "1") (pinfunction "1_1") (pintype "passive"))
      (node (ref "C105") (pin "1") (pinfunction "1_1") (pintype "passive"))
      (node (ref "C106") (pin "1") (pinfunction "1_1") (pintype "passive"))
      (node (ref "C107") (pin "1") (pinfunction "1_1") (pintype "passive"))
      (node (ref "C108") (pin "1") (pinfunction "1_1") (pintype "passive"))
      (node (ref "C109") (pin "1") (pinfunction "1_1") (pintype "passive"))
      (node (ref "C110") (pin "1") (pinfunction "1_1") (pintype "passive"))
      (node (ref "C111") (pin "1") (pinfunction "1_1") (pintype "passive"))
      (node (ref "C112") (pin "1") (pinfunction "1_1") (pintype "passive"))
      (node (ref "C113") (pin "1") (pinfunction "1_1") (pintype "passive"))
      (node (ref "C114") (pin "1") (pinfunction "1_1") (pintype "passive"))
      (node (ref "C115") (pin "1") (pinfunction "1_1") (pintype "passive"))
      (node (ref "C116") (pin "1") (pinfunction "1_1") (pintype "passive"))
      (node (ref "C117") (pin "1") (pinfunction "1_1") (pintype "passive"))
      (node (ref "C118") (pin "1") (pinfunction "1_1") (pintype "passive"))
      (node (ref "C119") (pin "1") (pinfunction "1_1") (pintype "passive"))
      (node (ref "C120") (pin "1") (pinfunction "1_1") (pintype "passive"))
      (node (ref "C121") (pin "1") (pinfunction "1_1") (pintype "passive"))
      (node (ref "C122") (pin "1") (pinfunction "1_1") (pintype "passive"))
      (node (ref "C123") (pin "1") (pinfunction "1_1") (pintype "passive"))
      (node (ref "C124") (pin "1") (pinfunction "1_1") (pintype "passive"))
      (node (ref "D20") (pin "A") (pinfunction "A_A") (pintype "passive"))
      (node (ref "D21") (pin "A") (pinfunction "A_A") (pintype "passive"))
      (node (ref "D43") (pin "A") (pinfunction "A_A") (pintype "passive"))
      (node (ref "D44") (pin "A") (pinfunction "A_A") (pintype "passive"))
      (node (ref "D45") (pin "K") (pinfunction "Cathode_K") (pintype "passive"))
      (node (ref "D66") (pin "A") (pinfunction "A_A") (pintype "passive"))
      (node (ref "D67") (pin "A") (pinfunction "A_A") (pintype "passive"))
      (node (ref "J14") (pin "0") (pinfunction "0_0") (pintype "passive"))
      (node (ref "Q12") (pin "D") (pinfunction "Drain_D") (pintype "passive"))
      (node (ref "Q13") (pin "D") (pinfunction "Drain_D") (pintype "passive"))
      (node (ref "Q20") (pin "D") (pinfunction "Drain_D") (pintype "passive"))
      (node (ref "Q21") (pin "D") (pinfunction "Drain_D") (pintype "passive"))
      (node (ref "Q4") (pin "D") (pinfunction "Drain_D") (pintype "passive"))
      (node (ref "Q5") (pin "D") (pinfunction "Drain_D") (pintype "passive"))
      (node (ref "R116") (pin "1") (pinfunction "1_1") (pintype "passive"))
      (node (ref "R117") (pin "1") (pinfunction "1_1") (pintype "passive"))
      (node (ref "R151") (pin "1") (pinfunction "1_1") (pintype "passive"))
      (node (ref "R152") (pin "1") (pinfunction "1_1") (pintype "passive"))
      (node (ref "R81") (pin "1") (pinfunction "1_1") (pintype "passive"))
      (node (ref "R82") (pin "1") (pinfunction "1_1") (pintype "passive"))
    )
    (net (code "91") (name "unconnected-(U9-NC-Pad1)") (class "Default")
      (node (ref "U9") (pin "1") (pinfunction "NC_1") (pintype "passive"))
    )
    (net (code "92") (name "unconnected-(U9-NC-Pad4)") (class "Default")
      (node (ref "U9") (pin "4") (pinfunction "NC_4") (pintype "passive"))
    )
    (net (code "93") (name "unconnected-(U12-NC-Pad1)") (class "Default")
      (node (ref "U12") (pin "1") (pinfunction "NC_1") (pintype "passive"))
    )
    (net (code "94") (name "unconnected-(U12-NC-Pad4)") (class "Default")
      (node (ref "U12") (pin "4") (pinfunction "NC_4") (pintype "passive"))
    )
    (net (code "95") (name "unconnected-(U13-NC-Pad3)") (class "Default")
      (node (ref "U13") (pin "3") (pinfunction "NC_3") (pintype "passive"))
    )
    (net (code "96") (name "unconnected-(U14-NC-Pad1)") (class "Default")
      (node (ref "U14") (pin "1") (pinfunction "NC_1") (pintype "passive"))
    )
    (net (code "97") (name "unconnected-(U14-NC-Pad4)") (class "Default")
      (node (ref "U14") (pin "4") (pinfunction "NC_4") (pintype "passive"))
    )
    (net (code "98") (name "unconnected-(U17-NC-Pad1)") (class "Default")
      (node (ref "U17") (pin "1") (pinfunction "NC_1") (pintype "passive"))
    )
    (net (code "99") (name "unconnected-(U17-NC-Pad4)") (class "Default")
      (node (ref "U17") (pin "4") (pinfunction "NC_4") (pintype "passive"))
    )
    (net (code "100") (name "unconnected-(U18-NC-Pad3)") (class "Default")
      (node (ref "U18") (pin "3") (pinfunction "NC_3") (pintype "passive"))
    )
    (net (code "101") (name "unconnected-(U19-NC-Pad1)") (class "Default")
      (node (ref "U19") (pin "1") (pinfunction "NC_1") (pintype "passive"))
    )
    (net (code "102") (name "unconnected-(U19-NC-Pad4)") (class "Default")
      (node (ref "U19") (pin "4") (pinfunction "NC_4") (pintype "passive"))
    )
    (net (code "103") (name "unconnected-(U22-NC-Pad1)") (class "Default")
      (node (ref "U22") (pin "1") (pinfunction "NC_1") (pintype "passive"))
    )
    (net (code "104") (name "unconnected-(U22-NC-Pad4)") (class "Default")
      (node (ref "U22") (pin "4") (pinfunction "NC_4") (pintype "passive"))
    )
    (net (code "105") (name "unconnected-(U23-NC-Pad3)") (class "Default")
      (node (ref "U23") (pin "3") (pinfunction "NC_3") (pintype "passive"))
    )
  )
)
